# BMS_MAINBOARD.net
KiCad netlist of a schematic drawn in Altium Designer
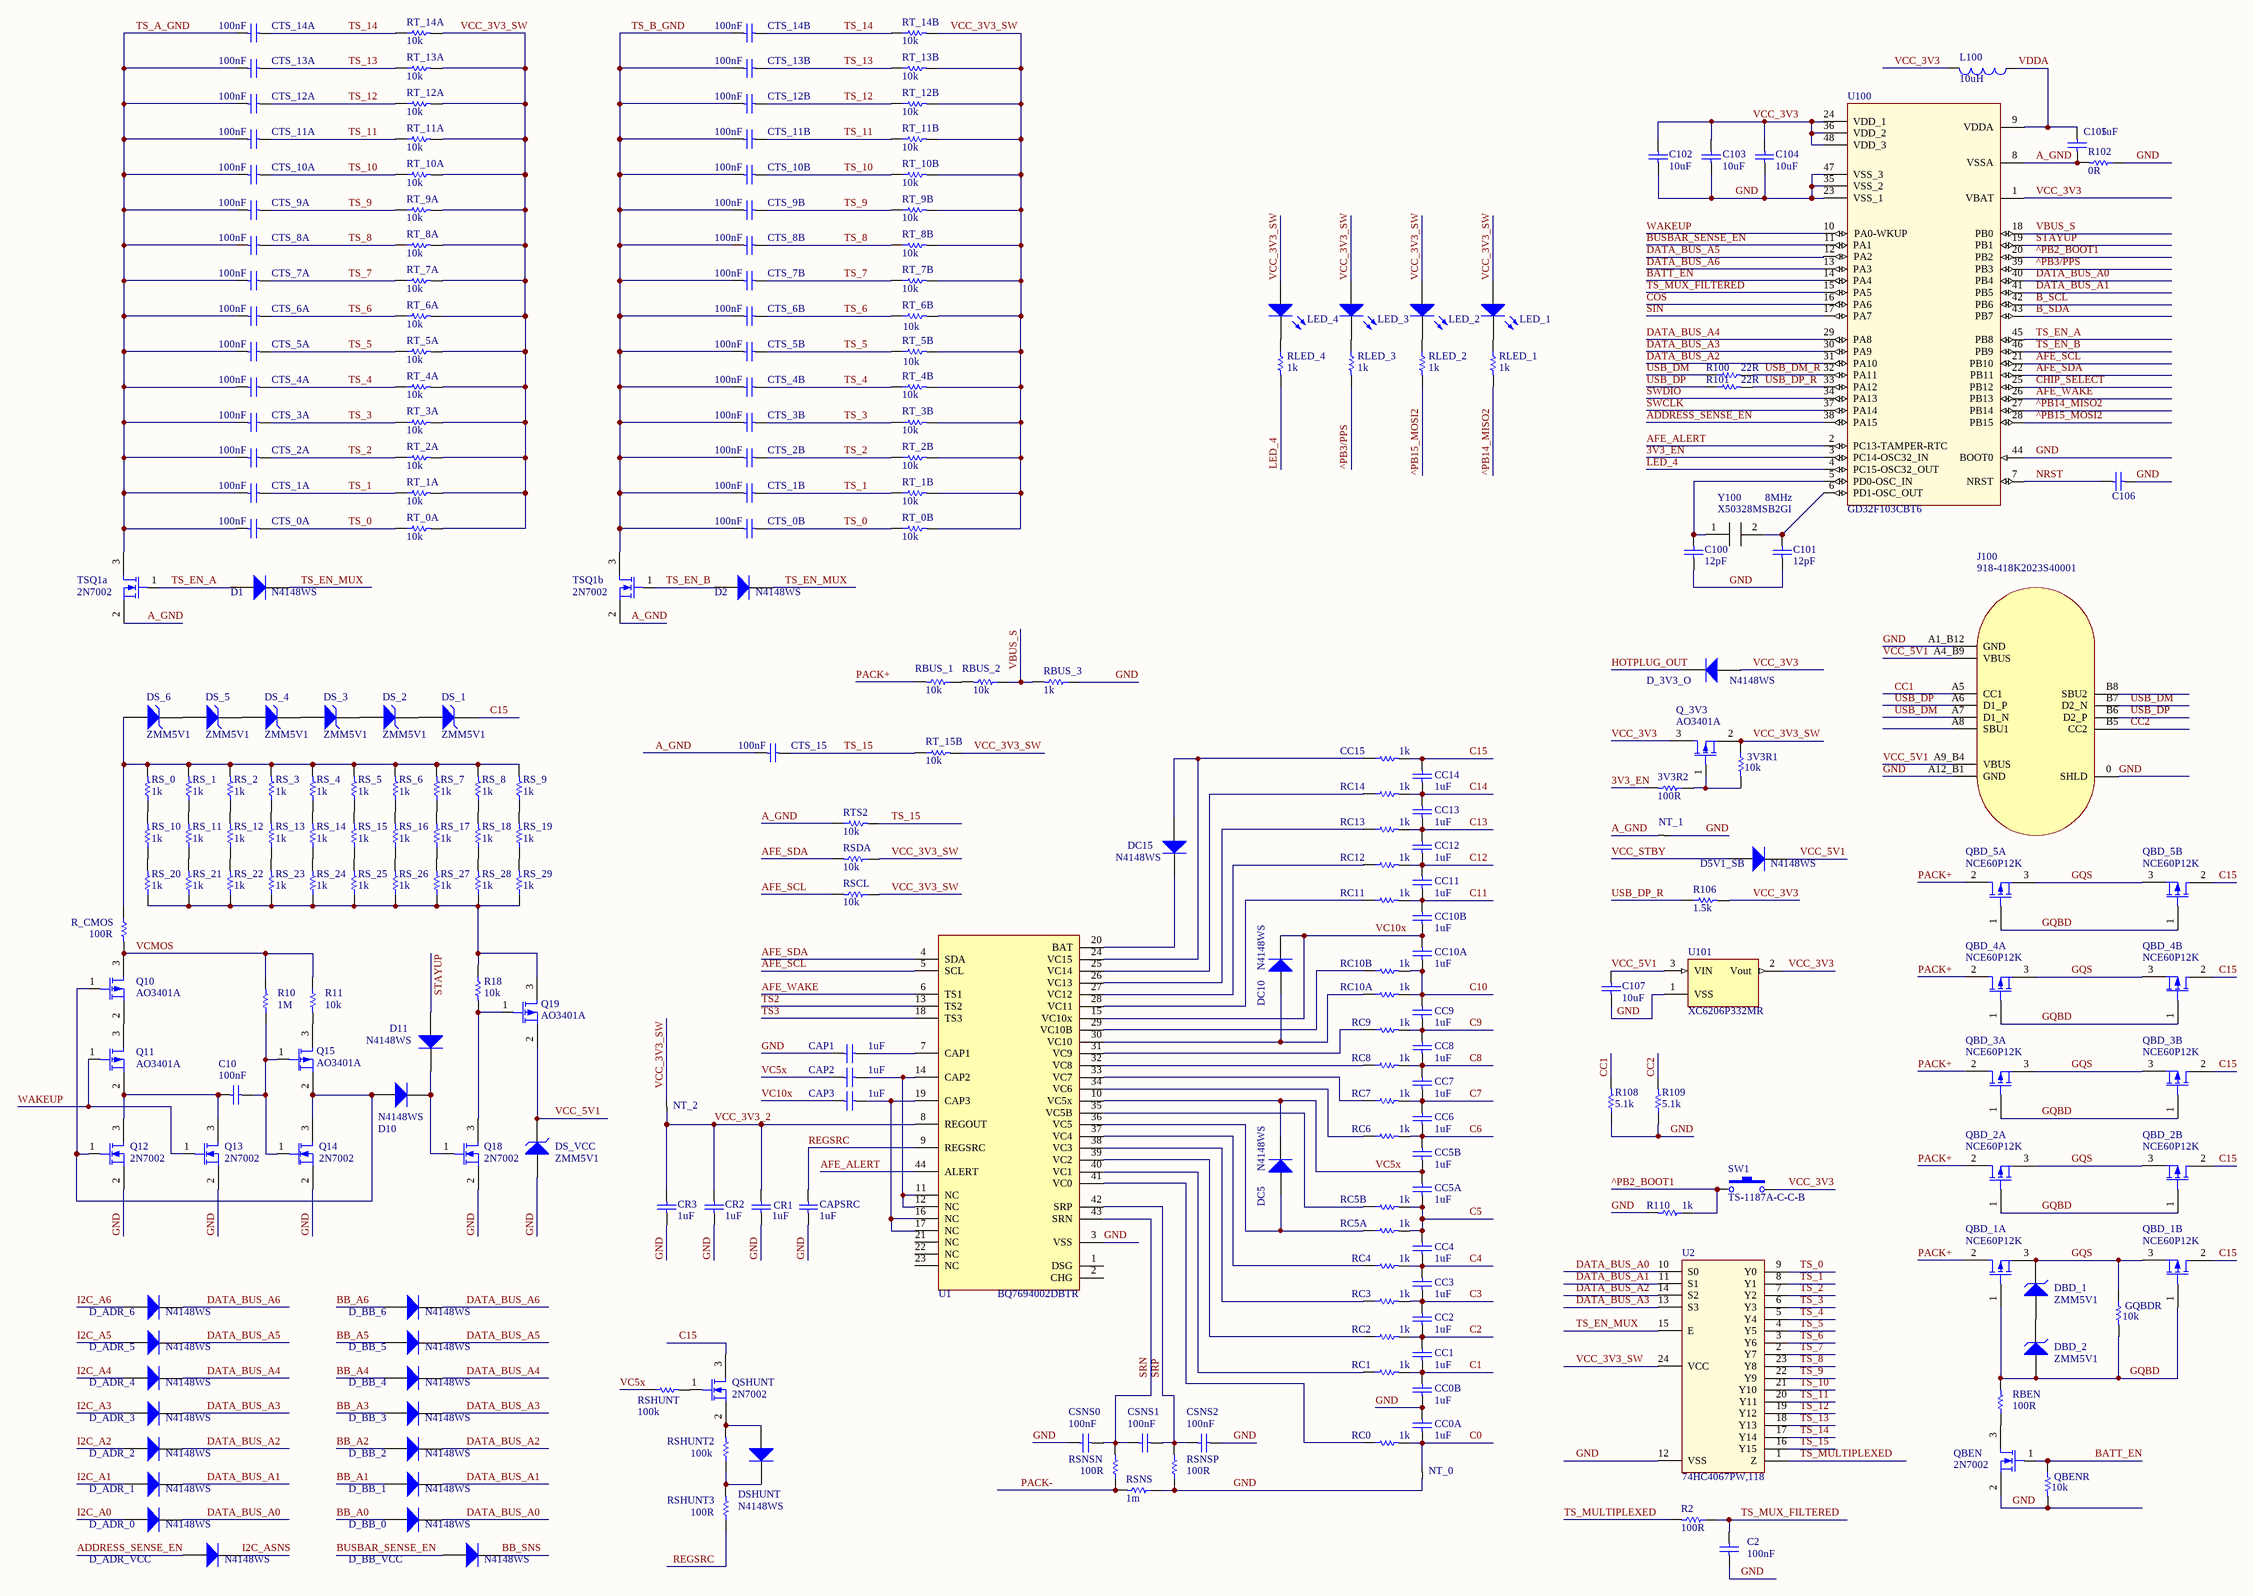
[diagram p0: BMS_MAINBOARD.SchDoc]

(export (version "E")
  (design (tool "Eeschema 10.0.6"))
  (components
    (comp (ref "3V3R1")
      (value "10k")
      (footprint "R_0402")
      (description "R - RESISTOR - SMD - 10k - 1% - 0402")
      (fields (field (name "LCSC PART #") "C25744") (field (name "Comment") "0402WGF1002TCE"))
      (libsource (lib "JLC_PCB") (part "0402WGF1002TCE"))
    )
    (comp (ref "3V3R2")
      (value "100R")
      (footprint "R_0402")
      (description "R - RESISTOR - SMD - 100R - 1% - 0402")
      (fields (field (name "LCSC PART #") "C25076") (field (name "Comment") "0402WGF1000TCE"))
      (libsource (lib "JLC_PCB") (part "0402WGF1000TCE"))
    )
    (comp (ref "C2")
      (value "100nF")
      (footprint "C_0402")
      (description "C - CAPACITOR - MLCC - 100nF - 16V - 0402")
      (fields (field (name "LCSC PART #") "C1525") (field (name "Comment") "CL05B104KO5NNNC"))
      (libsource (lib "JLC_PCB") (part "CL05B104KO5NNNC"))
    )
    (comp (ref "C10")
      (value "100nF")
      (footprint "C_0402")
      (description "C - CAPACITOR - MLCC - 100nF - 16V - 0402")
      (fields (field (name "LCSC PART #") "C1525") (field (name "Comment") "CL05B104KO5NNNC"))
      (libsource (lib "JLC_PCB") (part "CL05B104KO5NNNC"))
    )
    (comp (ref "C100")
      (value "12pF")
      (footprint "C_0402")
      (description "C - CAPACITOR - MLCC - 12pF - 50V - 0402")
      (fields (field (name "LCSC PART #") "C1547") (field (name "Comment") "0402CG120J500NT"))
      (libsource (lib "JLC_PCB") (part "0402CG120J500NT"))
    )
    (comp (ref "C101")
      (value "12pF")
      (footprint "C_0402")
      (description "C - CAPACITOR - MLCC - 12pF - 50V - 0402")
      (fields (field (name "LCSC PART #") "C1547") (field (name "Comment") "0402CG120J500NT"))
      (libsource (lib "JLC_PCB") (part "0402CG120J500NT"))
    )
    (comp (ref "C102")
      (value "10uF")
      (footprint "C_0402")
      (description "C - CAPACITOR - MLCC - 10uF - 6.3V - 0402")
      (fields (field (name "LCSC PART #") "C15525") (field (name "Comment") "CL05A106MQ5NUNC"))
      (libsource (lib "JLC_PCB") (part "CL05A106MQ5NUNC"))
    )
    (comp (ref "C103")
      (value "10uF")
      (footprint "C_0402")
      (description "C - CAPACITOR - MLCC - 10uF - 6.3V - 0402")
      (fields (field (name "LCSC PART #") "C15525") (field (name "Comment") "CL05A106MQ5NUNC"))
      (libsource (lib "JLC_PCB") (part "CL05A106MQ5NUNC"))
    )
    (comp (ref "C104")
      (value "10uF")
      (footprint "C_0402")
      (description "C - CAPACITOR - MLCC - 10uF - 6.3V - 0402")
      (fields (field (name "LCSC PART #") "C15525") (field (name "Comment") "CL05A106MQ5NUNC"))
      (libsource (lib "JLC_PCB") (part "CL05A106MQ5NUNC"))
    )
    (comp (ref "C105")
      (value "1uF")
      (footprint "C_0402")
      (description "C - CAPACITOR - MLCC - 1uF - 25V - 0402")
      (fields (field (name "LCSC PART #") "C52923") (field (name "Comment") "CL05A105KA5NQNC"))
      (libsource (lib "JLC_PCB") (part "CL05A105KA5NQNC"))
    )
    (comp (ref "C106")
      (value "0402CG101J500NT")
      (footprint "C_0402")
      (description "C - CAPACITOR - MLCC - 100pF - 50V - 0402")
      (fields (field (name "LCSC PART #") "C1546"))
      (libsource (lib "JLC_PCB") (part "0402CG101J500NT"))
    )
    (comp (ref "C107")
      (value "10uF")
      (footprint "C_0402")
      (description "C - CAPACITOR - MLCC - 10uF - 6.3V - 0402")
      (fields (field (name "LCSC PART #") "C15525") (field (name "Comment") "CL05A106MQ5NUNC"))
      (libsource (lib "JLC_PCB") (part "CL05A106MQ5NUNC"))
    )
    (comp (ref "CAP1")
      (value "1uF")
      (footprint "C_0402")
      (description "C - CAPACITOR - MLCC - 1uF - 25V - 0402")
      (fields (field (name "LCSC PART #") "C52923") (field (name "Comment") "CL05A105KA5NQNC"))
      (libsource (lib "JLC_PCB") (part "CL05A105KA5NQNC"))
    )
    (comp (ref "CAP2")
      (value "1uF")
      (footprint "C_0402")
      (description "C - CAPACITOR - MLCC - 1uF - 25V - 0402")
      (fields (field (name "LCSC PART #") "C52923") (field (name "Comment") "CL05A105KA5NQNC"))
      (libsource (lib "JLC_PCB") (part "CL05A105KA5NQNC"))
    )
    (comp (ref "CAP3")
      (value "1uF")
      (footprint "C_0402")
      (description "C - CAPACITOR - MLCC - 1uF - 25V - 0402")
      (fields (field (name "LCSC PART #") "C52923") (field (name "Comment") "CL05A105KA5NQNC"))
      (libsource (lib "JLC_PCB") (part "CL05A105KA5NQNC"))
    )
    (comp (ref "CAPSRC")
      (value "1uF")
      (footprint "C_0402")
      (description "C - CAPACITOR - MLCC - 1uF - 25V - 0402")
      (fields (field (name "LCSC PART #") "C52923") (field (name "Comment") "CL05A105KA5NQNC"))
      (libsource (lib "JLC_PCB") (part "CL05A105KA5NQNC"))
    )
    (comp (ref "CC0A")
      (value "1uF")
      (footprint "C_0402")
      (description "C - CAPACITOR - MLCC - 1uF - 25V - 0402")
      (fields (field (name "LCSC PART #") "C52923") (field (name "Comment") "CL05A105KA5NQNC"))
      (libsource (lib "JLC_PCB") (part "CL05A105KA5NQNC"))
    )
    (comp (ref "CC0B")
      (value "1uF")
      (footprint "C_0402")
      (description "C - CAPACITOR - MLCC - 1uF - 25V - 0402")
      (fields (field (name "LCSC PART #") "C52923") (field (name "Comment") "CL05A105KA5NQNC"))
      (libsource (lib "JLC_PCB") (part "CL05A105KA5NQNC"))
    )
    (comp (ref "CC1")
      (value "1uF")
      (footprint "C_0402")
      (description "C - CAPACITOR - MLCC - 1uF - 25V - 0402")
      (fields (field (name "LCSC PART #") "C52923") (field (name "Comment") "CL05A105KA5NQNC"))
      (libsource (lib "JLC_PCB") (part "CL05A105KA5NQNC"))
    )
    (comp (ref "CC2")
      (value "1uF")
      (footprint "C_0402")
      (description "C - CAPACITOR - MLCC - 1uF - 25V - 0402")
      (fields (field (name "LCSC PART #") "C52923") (field (name "Comment") "CL05A105KA5NQNC"))
      (libsource (lib "JLC_PCB") (part "CL05A105KA5NQNC"))
    )
    (comp (ref "CC3")
      (value "1uF")
      (footprint "C_0402")
      (description "C - CAPACITOR - MLCC - 1uF - 25V - 0402")
      (fields (field (name "LCSC PART #") "C52923") (field (name "Comment") "CL05A105KA5NQNC"))
      (libsource (lib "JLC_PCB") (part "CL05A105KA5NQNC"))
    )
    (comp (ref "CC4")
      (value "1uF")
      (footprint "C_0402")
      (description "C - CAPACITOR - MLCC - 1uF - 25V - 0402")
      (fields (field (name "LCSC PART #") "C52923") (field (name "Comment") "CL05A105KA5NQNC"))
      (libsource (lib "JLC_PCB") (part "CL05A105KA5NQNC"))
    )
    (comp (ref "CC5A")
      (value "1uF")
      (footprint "C_0402")
      (description "C - CAPACITOR - MLCC - 1uF - 25V - 0402")
      (fields (field (name "LCSC PART #") "C52923") (field (name "Comment") "CL05A105KA5NQNC"))
      (libsource (lib "JLC_PCB") (part "CL05A105KA5NQNC"))
    )
    (comp (ref "CC5B")
      (value "1uF")
      (footprint "C_0402")
      (description "C - CAPACITOR - MLCC - 1uF - 25V - 0402")
      (fields (field (name "LCSC PART #") "C52923") (field (name "Comment") "CL05A105KA5NQNC"))
      (libsource (lib "JLC_PCB") (part "CL05A105KA5NQNC"))
    )
    (comp (ref "CC6")
      (value "1uF")
      (footprint "C_0402")
      (description "C - CAPACITOR - MLCC - 1uF - 25V - 0402")
      (fields (field (name "LCSC PART #") "C52923") (field (name "Comment") "CL05A105KA5NQNC"))
      (libsource (lib "JLC_PCB") (part "CL05A105KA5NQNC"))
    )
    (comp (ref "CC7")
      (value "1uF")
      (footprint "C_0402")
      (description "C - CAPACITOR - MLCC - 1uF - 25V - 0402")
      (fields (field (name "LCSC PART #") "C52923") (field (name "Comment") "CL05A105KA5NQNC"))
      (libsource (lib "JLC_PCB") (part "CL05A105KA5NQNC"))
    )
    (comp (ref "CC8")
      (value "1uF")
      (footprint "C_0402")
      (description "C - CAPACITOR - MLCC - 1uF - 25V - 0402")
      (fields (field (name "LCSC PART #") "C52923") (field (name "Comment") "CL05A105KA5NQNC"))
      (libsource (lib "JLC_PCB") (part "CL05A105KA5NQNC"))
    )
    (comp (ref "CC9")
      (value "1uF")
      (footprint "C_0402")
      (description "C - CAPACITOR - MLCC - 1uF - 25V - 0402")
      (fields (field (name "LCSC PART #") "C52923") (field (name "Comment") "CL05A105KA5NQNC"))
      (libsource (lib "JLC_PCB") (part "CL05A105KA5NQNC"))
    )
    (comp (ref "CC10A")
      (value "1uF")
      (footprint "C_0402")
      (description "C - CAPACITOR - MLCC - 1uF - 25V - 0402")
      (fields (field (name "LCSC PART #") "C52923") (field (name "Comment") "CL05A105KA5NQNC"))
      (libsource (lib "JLC_PCB") (part "CL05A105KA5NQNC"))
    )
    (comp (ref "CC10B")
      (value "1uF")
      (footprint "C_0402")
      (description "C - CAPACITOR - MLCC - 1uF - 25V - 0402")
      (fields (field (name "LCSC PART #") "C52923") (field (name "Comment") "CL05A105KA5NQNC"))
      (libsource (lib "JLC_PCB") (part "CL05A105KA5NQNC"))
    )
    (comp (ref "CC11")
      (value "1uF")
      (footprint "C_0402")
      (description "C - CAPACITOR - MLCC - 1uF - 25V - 0402")
      (fields (field (name "LCSC PART #") "C52923") (field (name "Comment") "CL05A105KA5NQNC"))
      (libsource (lib "JLC_PCB") (part "CL05A105KA5NQNC"))
    )
    (comp (ref "CC12")
      (value "1uF")
      (footprint "C_0402")
      (description "C - CAPACITOR - MLCC - 1uF - 25V - 0402")
      (fields (field (name "LCSC PART #") "C52923") (field (name "Comment") "CL05A105KA5NQNC"))
      (libsource (lib "JLC_PCB") (part "CL05A105KA5NQNC"))
    )
    (comp (ref "CC13")
      (value "1uF")
      (footprint "C_0402")
      (description "C - CAPACITOR - MLCC - 1uF - 25V - 0402")
      (fields (field (name "LCSC PART #") "C52923") (field (name "Comment") "CL05A105KA5NQNC"))
      (libsource (lib "JLC_PCB") (part "CL05A105KA5NQNC"))
    )
    (comp (ref "CC14")
      (value "1uF")
      (footprint "C_0402")
      (description "C - CAPACITOR - MLCC - 1uF - 25V - 0402")
      (fields (field (name "LCSC PART #") "C52923") (field (name "Comment") "CL05A105KA5NQNC"))
      (libsource (lib "JLC_PCB") (part "CL05A105KA5NQNC"))
    )
    (comp (ref "CC15")
      (value "1k")
      (footprint "R_0402")
      (description "R - RESISTOR - SMD - 1k - 1% - 0402")
      (fields (field (name "LCSC PART #") "C11702") (field (name "Comment") "0402WGF1001TCE"))
      (libsource (lib "JLC_PCB") (part "0402WGF1001TCE"))
    )
    (comp (ref "CR1")
      (value "1uF")
      (footprint "C_0402")
      (description "C - CAPACITOR - MLCC - 1uF - 25V - 0402")
      (fields (field (name "LCSC PART #") "C52923") (field (name "Comment") "CL05A105KA5NQNC"))
      (libsource (lib "JLC_PCB") (part "CL05A105KA5NQNC"))
    )
    (comp (ref "CR2")
      (value "1uF")
      (footprint "C_0402")
      (description "C - CAPACITOR - MLCC - 1uF - 25V - 0402")
      (fields (field (name "LCSC PART #") "C52923") (field (name "Comment") "CL05A105KA5NQNC"))
      (libsource (lib "JLC_PCB") (part "CL05A105KA5NQNC"))
    )
    (comp (ref "CR3")
      (value "1uF")
      (footprint "C_0402")
      (description "C - CAPACITOR - MLCC - 1uF - 25V - 0402")
      (fields (field (name "LCSC PART #") "C52923") (field (name "Comment") "CL05A105KA5NQNC"))
      (libsource (lib "JLC_PCB") (part "CL05A105KA5NQNC"))
    )
    (comp (ref "CSNS0")
      (value "100nF")
      (footprint "C_0402")
      (description "C - CAPACITOR - MLCC - 100nF - 16V - 0402")
      (fields (field (name "LCSC PART #") "C1525") (field (name "Comment") "CL05B104KO5NNNC"))
      (libsource (lib "JLC_PCB") (part "CL05B104KO5NNNC"))
    )
    (comp (ref "CSNS1")
      (value "100nF")
      (footprint "C_0402")
      (description "C - CAPACITOR - MLCC - 100nF - 16V - 0402")
      (fields (field (name "LCSC PART #") "C1525") (field (name "Comment") "CL05B104KO5NNNC"))
      (libsource (lib "JLC_PCB") (part "CL05B104KO5NNNC"))
    )
    (comp (ref "CSNS2")
      (value "100nF")
      (footprint "C_0402")
      (description "C - CAPACITOR - MLCC - 100nF - 16V - 0402")
      (fields (field (name "LCSC PART #") "C1525") (field (name "Comment") "CL05B104KO5NNNC"))
      (libsource (lib "JLC_PCB") (part "CL05B104KO5NNNC"))
    )
    (comp (ref "CTS_0A")
      (value "100nF")
      (footprint "C_0402")
      (description "C - CAPACITOR - MLCC - 100nF - 16V - 0402")
      (fields (field (name "LCSC PART #") "C1525") (field (name "Comment") "CL05B104KO5NNNC"))
      (libsource (lib "JLC_PCB") (part "CL05B104KO5NNNC"))
    )
    (comp (ref "CTS_0B")
      (value "100nF")
      (footprint "C_0402")
      (description "C - CAPACITOR - MLCC - 100nF - 16V - 0402")
      (fields (field (name "LCSC PART #") "C1525") (field (name "Comment") "CL05B104KO5NNNC"))
      (libsource (lib "JLC_PCB") (part "CL05B104KO5NNNC"))
    )
    (comp (ref "CTS_1A")
      (value "100nF")
      (footprint "C_0402")
      (description "C - CAPACITOR - MLCC - 100nF - 16V - 0402")
      (fields (field (name "LCSC PART #") "C1525") (field (name "Comment") "CL05B104KO5NNNC"))
      (libsource (lib "JLC_PCB") (part "CL05B104KO5NNNC"))
    )
    (comp (ref "CTS_1B")
      (value "100nF")
      (footprint "C_0402")
      (description "C - CAPACITOR - MLCC - 100nF - 16V - 0402")
      (fields (field (name "LCSC PART #") "C1525") (field (name "Comment") "CL05B104KO5NNNC"))
      (libsource (lib "JLC_PCB") (part "CL05B104KO5NNNC"))
    )
    (comp (ref "CTS_2A")
      (value "100nF")
      (footprint "C_0402")
      (description "C - CAPACITOR - MLCC - 100nF - 16V - 0402")
      (fields (field (name "LCSC PART #") "C1525") (field (name "Comment") "CL05B104KO5NNNC"))
      (libsource (lib "JLC_PCB") (part "CL05B104KO5NNNC"))
    )
    (comp (ref "CTS_2B")
      (value "100nF")
      (footprint "C_0402")
      (description "C - CAPACITOR - MLCC - 100nF - 16V - 0402")
      (fields (field (name "LCSC PART #") "C1525") (field (name "Comment") "CL05B104KO5NNNC"))
      (libsource (lib "JLC_PCB") (part "CL05B104KO5NNNC"))
    )
    (comp (ref "CTS_3A")
      (value "100nF")
      (footprint "C_0402")
      (description "C - CAPACITOR - MLCC - 100nF - 16V - 0402")
      (fields (field (name "LCSC PART #") "C1525") (field (name "Comment") "CL05B104KO5NNNC"))
      (libsource (lib "JLC_PCB") (part "CL05B104KO5NNNC"))
    )
    (comp (ref "CTS_3B")
      (value "100nF")
      (footprint "C_0402")
      (description "C - CAPACITOR - MLCC - 100nF - 16V - 0402")
      (fields (field (name "LCSC PART #") "C1525") (field (name "Comment") "CL05B104KO5NNNC"))
      (libsource (lib "JLC_PCB") (part "CL05B104KO5NNNC"))
    )
    (comp (ref "CTS_4A")
      (value "100nF")
      (footprint "C_0402")
      (description "C - CAPACITOR - MLCC - 100nF - 16V - 0402")
      (fields (field (name "LCSC PART #") "C1525") (field (name "Comment") "CL05B104KO5NNNC"))
      (libsource (lib "JLC_PCB") (part "CL05B104KO5NNNC"))
    )
    (comp (ref "CTS_4B")
      (value "100nF")
      (footprint "C_0402")
      (description "C - CAPACITOR - MLCC - 100nF - 16V - 0402")
      (fields (field (name "LCSC PART #") "C1525") (field (name "Comment") "CL05B104KO5NNNC"))
      (libsource (lib "JLC_PCB") (part "CL05B104KO5NNNC"))
    )
    (comp (ref "CTS_5A")
      (value "100nF")
      (footprint "C_0402")
      (description "C - CAPACITOR - MLCC - 100nF - 16V - 0402")
      (fields (field (name "LCSC PART #") "C1525") (field (name "Comment") "CL05B104KO5NNNC"))
      (libsource (lib "JLC_PCB") (part "CL05B104KO5NNNC"))
    )
    (comp (ref "CTS_5B")
      (value "100nF")
      (footprint "C_0402")
      (description "C - CAPACITOR - MLCC - 100nF - 16V - 0402")
      (fields (field (name "LCSC PART #") "C1525") (field (name "Comment") "CL05B104KO5NNNC"))
      (libsource (lib "JLC_PCB") (part "CL05B104KO5NNNC"))
    )
    (comp (ref "CTS_6A")
      (value "100nF")
      (footprint "C_0402")
      (description "C - CAPACITOR - MLCC - 100nF - 16V - 0402")
      (fields (field (name "LCSC PART #") "C1525") (field (name "Comment") "CL05B104KO5NNNC"))
      (libsource (lib "JLC_PCB") (part "CL05B104KO5NNNC"))
    )
    (comp (ref "CTS_6B")
      (value "100nF")
      (footprint "C_0402")
      (description "C - CAPACITOR - MLCC - 100nF - 16V - 0402")
      (fields (field (name "LCSC PART #") "C1525") (field (name "Comment") "CL05B104KO5NNNC"))
      (libsource (lib "JLC_PCB") (part "CL05B104KO5NNNC"))
    )
    (comp (ref "CTS_7A")
      (value "100nF")
      (footprint "C_0402")
      (description "C - CAPACITOR - MLCC - 100nF - 16V - 0402")
      (fields (field (name "LCSC PART #") "C1525") (field (name "Comment") "CL05B104KO5NNNC"))
      (libsource (lib "JLC_PCB") (part "CL05B104KO5NNNC"))
    )
    (comp (ref "CTS_7B")
      (value "100nF")
      (footprint "C_0402")
      (description "C - CAPACITOR - MLCC - 100nF - 16V - 0402")
      (fields (field (name "LCSC PART #") "C1525") (field (name "Comment") "CL05B104KO5NNNC"))
      (libsource (lib "JLC_PCB") (part "CL05B104KO5NNNC"))
    )
    (comp (ref "CTS_8A")
      (value "100nF")
      (footprint "C_0402")
      (description "C - CAPACITOR - MLCC - 100nF - 16V - 0402")
      (fields (field (name "LCSC PART #") "C1525") (field (name "Comment") "CL05B104KO5NNNC"))
      (libsource (lib "JLC_PCB") (part "CL05B104KO5NNNC"))
    )
    (comp (ref "CTS_8B")
      (value "100nF")
      (footprint "C_0402")
      (description "C - CAPACITOR - MLCC - 100nF - 16V - 0402")
      (fields (field (name "LCSC PART #") "C1525") (field (name "Comment") "CL05B104KO5NNNC"))
      (libsource (lib "JLC_PCB") (part "CL05B104KO5NNNC"))
    )
    (comp (ref "CTS_9A")
      (value "100nF")
      (footprint "C_0402")
      (description "C - CAPACITOR - MLCC - 100nF - 16V - 0402")
      (fields (field (name "LCSC PART #") "C1525") (field (name "Comment") "CL05B104KO5NNNC"))
      (libsource (lib "JLC_PCB") (part "CL05B104KO5NNNC"))
    )
    (comp (ref "CTS_9B")
      (value "100nF")
      (footprint "C_0402")
      (description "C - CAPACITOR - MLCC - 100nF - 16V - 0402")
      (fields (field (name "LCSC PART #") "C1525") (field (name "Comment") "CL05B104KO5NNNC"))
      (libsource (lib "JLC_PCB") (part "CL05B104KO5NNNC"))
    )
    (comp (ref "CTS_10A")
      (value "100nF")
      (footprint "C_0402")
      (description "C - CAPACITOR - MLCC - 100nF - 16V - 0402")
      (fields (field (name "LCSC PART #") "C1525") (field (name "Comment") "CL05B104KO5NNNC"))
      (libsource (lib "JLC_PCB") (part "CL05B104KO5NNNC"))
    )
    (comp (ref "CTS_10B")
      (value "100nF")
      (footprint "C_0402")
      (description "C - CAPACITOR - MLCC - 100nF - 16V - 0402")
      (fields (field (name "LCSC PART #") "C1525") (field (name "Comment") "CL05B104KO5NNNC"))
      (libsource (lib "JLC_PCB") (part "CL05B104KO5NNNC"))
    )
    (comp (ref "CTS_11A")
      (value "100nF")
      (footprint "C_0402")
      (description "C - CAPACITOR - MLCC - 100nF - 16V - 0402")
      (fields (field (name "LCSC PART #") "C1525") (field (name "Comment") "CL05B104KO5NNNC"))
      (libsource (lib "JLC_PCB") (part "CL05B104KO5NNNC"))
    )
    (comp (ref "CTS_11B")
      (value "100nF")
      (footprint "C_0402")
      (description "C - CAPACITOR - MLCC - 100nF - 16V - 0402")
      (fields (field (name "LCSC PART #") "C1525") (field (name "Comment") "CL05B104KO5NNNC"))
      (libsource (lib "JLC_PCB") (part "CL05B104KO5NNNC"))
    )
    (comp (ref "CTS_12A")
      (value "100nF")
      (footprint "C_0402")
      (description "C - CAPACITOR - MLCC - 100nF - 16V - 0402")
      (fields (field (name "LCSC PART #") "C1525") (field (name "Comment") "CL05B104KO5NNNC"))
      (libsource (lib "JLC_PCB") (part "CL05B104KO5NNNC"))
    )
    (comp (ref "CTS_12B")
      (value "100nF")
      (footprint "C_0402")
      (description "C - CAPACITOR - MLCC - 100nF - 16V - 0402")
      (fields (field (name "LCSC PART #") "C1525") (field (name "Comment") "CL05B104KO5NNNC"))
      (libsource (lib "JLC_PCB") (part "CL05B104KO5NNNC"))
    )
    (comp (ref "CTS_13A")
      (value "100nF")
      (footprint "C_0402")
      (description "C - CAPACITOR - MLCC - 100nF - 16V - 0402")
      (fields (field (name "LCSC PART #") "C1525") (field (name "Comment") "CL05B104KO5NNNC"))
      (libsource (lib "JLC_PCB") (part "CL05B104KO5NNNC"))
    )
    (comp (ref "CTS_13B")
      (value "100nF")
      (footprint "C_0402")
      (description "C - CAPACITOR - MLCC - 100nF - 16V - 0402")
      (fields (field (name "LCSC PART #") "C1525") (field (name "Comment") "CL05B104KO5NNNC"))
      (libsource (lib "JLC_PCB") (part "CL05B104KO5NNNC"))
    )
    (comp (ref "CTS_14A")
      (value "100nF")
      (footprint "C_0402")
      (description "C - CAPACITOR - MLCC - 100nF - 16V - 0402")
      (fields (field (name "LCSC PART #") "C1525") (field (name "Comment") "CL05B104KO5NNNC"))
      (libsource (lib "JLC_PCB") (part "CL05B104KO5NNNC"))
    )
    (comp (ref "CTS_14B")
      (value "100nF")
      (footprint "C_0402")
      (description "C - CAPACITOR - MLCC - 100nF - 16V - 0402")
      (fields (field (name "LCSC PART #") "C1525") (field (name "Comment") "CL05B104KO5NNNC"))
      (libsource (lib "JLC_PCB") (part "CL05B104KO5NNNC"))
    )
    (comp (ref "CTS_15")
      (value "100nF")
      (footprint "C_0402")
      (description "C - CAPACITOR - MLCC - 100nF - 16V - 0402")
      (fields (field (name "LCSC PART #") "C1525") (field (name "Comment") "CL05B104KO5NNNC"))
      (libsource (lib "JLC_PCB") (part "CL05B104KO5NNNC"))
    )
    (comp (ref "D1")
      (value "N4148WS")
      (footprint "SOD-323")
      (description "D - DIODE - FAST TRR - 100V - 150mA - 4ns")
      (fields (field (name "LCSC PART #") "C2128"))
      (libsource (lib "JLC_PCB") (part "N4148WS"))
    )
    (comp (ref "D2")
      (value "N4148WS")
      (footprint "SOD-323")
      (description "D - DIODE - FAST TRR - 100V - 150mA - 4ns")
      (fields (field (name "LCSC PART #") "C2128"))
      (libsource (lib "JLC_PCB") (part "N4148WS"))
    )
    (comp (ref "D5V1_SB")
      (value "N4148WS")
      (footprint "SOD-323")
      (description "D - DIODE - FAST TRR - 100V - 150mA - 4ns")
      (fields (field (name "LCSC PART #") "C2128"))
      (libsource (lib "JLC_PCB") (part "N4148WS"))
    )
    (comp (ref "D10")
      (value "N4148WS")
      (footprint "SOD-323")
      (description "D - DIODE - FAST TRR - 100V - 150mA - 4ns")
      (fields (field (name "LCSC PART #") "C2128"))
      (libsource (lib "JLC_PCB") (part "N4148WS"))
    )
    (comp (ref "D11")
      (value "N4148WS")
      (footprint "SOD-323")
      (description "D - DIODE - FAST TRR - 100V - 150mA - 4ns")
      (fields (field (name "LCSC PART #") "C2128"))
      (libsource (lib "JLC_PCB") (part "N4148WS"))
    )
    (comp (ref "DBD_1")
      (value "ZMM5V1")
      (footprint "DO-213AA")
      (description "D - DIODE - ZENER - 5.1V - 500mW")
      (fields (field (name "LCSC PART #") "C8061"))
      (libsource (lib "JLC_PCB") (part "ZMM5V1"))
    )
    (comp (ref "DBD_2")
      (value "ZMM5V1")
      (footprint "DO-213AA")
      (description "D - DIODE - ZENER - 5.1V - 500mW")
      (fields (field (name "LCSC PART #") "C8061"))
      (libsource (lib "JLC_PCB") (part "ZMM5V1"))
    )
    (comp (ref "DC5")
      (value "N4148WS")
      (footprint "SOD-323")
      (description "D - DIODE - FAST TRR - 100V - 150mA - 4ns")
      (fields (field (name "LCSC PART #") "C2128"))
      (libsource (lib "JLC_PCB") (part "N4148WS"))
    )
    (comp (ref "DC10")
      (value "N4148WS")
      (footprint "SOD-323")
      (description "D - DIODE - FAST TRR - 100V - 150mA - 4ns")
      (fields (field (name "LCSC PART #") "C2128"))
      (libsource (lib "JLC_PCB") (part "N4148WS"))
    )
    (comp (ref "DC15")
      (value "N4148WS")
      (footprint "SOD-323")
      (description "D - DIODE - FAST TRR - 100V - 150mA - 4ns")
      (fields (field (name "LCSC PART #") "C2128"))
      (libsource (lib "JLC_PCB") (part "N4148WS"))
    )
    (comp (ref "DSHUNT")
      (value "N4148WS")
      (footprint "SOD-323")
      (description "D - DIODE - FAST TRR - 100V - 150mA - 4ns")
      (fields (field (name "LCSC PART #") "C2128"))
      (libsource (lib "JLC_PCB") (part "N4148WS"))
    )
    (comp (ref "DS_1")
      (value "ZMM5V1")
      (footprint "DO-213AA")
      (description "D - DIODE - ZENER - 5.1V - 500mW")
      (fields (field (name "LCSC PART #") "C8061"))
      (libsource (lib "JLC_PCB") (part "ZMM5V1"))
    )
    (comp (ref "DS_2")
      (value "ZMM5V1")
      (footprint "DO-213AA")
      (description "D - DIODE - ZENER - 5.1V - 500mW")
      (fields (field (name "LCSC PART #") "C8061"))
      (libsource (lib "JLC_PCB") (part "ZMM5V1"))
    )
    (comp (ref "DS_3")
      (value "ZMM5V1")
      (footprint "DO-213AA")
      (description "D - DIODE - ZENER - 5.1V - 500mW")
      (fields (field (name "LCSC PART #") "C8061"))
      (libsource (lib "JLC_PCB") (part "ZMM5V1"))
    )
    (comp (ref "DS_4")
      (value "ZMM5V1")
      (footprint "DO-213AA")
      (description "D - DIODE - ZENER - 5.1V - 500mW")
      (fields (field (name "LCSC PART #") "C8061"))
      (libsource (lib "JLC_PCB") (part "ZMM5V1"))
    )
    (comp (ref "DS_5")
      (value "ZMM5V1")
      (footprint "DO-213AA")
      (description "D - DIODE - ZENER - 5.1V - 500mW")
      (fields (field (name "LCSC PART #") "C8061"))
      (libsource (lib "JLC_PCB") (part "ZMM5V1"))
    )
    (comp (ref "DS_6")
      (value "ZMM5V1")
      (footprint "DO-213AA")
      (description "D - DIODE - ZENER - 5.1V - 500mW")
      (fields (field (name "LCSC PART #") "C8061"))
      (libsource (lib "JLC_PCB") (part "ZMM5V1"))
    )
    (comp (ref "DS_VCC")
      (value "ZMM5V1")
      (footprint "DO-213AA")
      (description "D - DIODE - ZENER - 5.1V - 500mW")
      (fields (field (name "LCSC PART #") "C8061"))
      (libsource (lib "JLC_PCB") (part "ZMM5V1"))
    )
    (comp (ref "D_3V3_O")
      (value "N4148WS")
      (footprint "SOD-323")
      (description "D - DIODE - FAST TRR - 100V - 150mA - 4ns")
      (fields (field (name "LCSC PART #") "C2128"))
      (libsource (lib "JLC_PCB") (part "N4148WS"))
    )
    (comp (ref "D_ADR_0")
      (value "N4148WS")
      (footprint "SOD-323")
      (description "D - DIODE - FAST TRR - 100V - 150mA - 4ns")
      (fields (field (name "LCSC PART #") "C2128"))
      (libsource (lib "JLC_PCB") (part "N4148WS"))
    )
    (comp (ref "D_ADR_1")
      (value "N4148WS")
      (footprint "SOD-323")
      (description "D - DIODE - FAST TRR - 100V - 150mA - 4ns")
      (fields (field (name "LCSC PART #") "C2128"))
      (libsource (lib "JLC_PCB") (part "N4148WS"))
    )
    (comp (ref "D_ADR_2")
      (value "N4148WS")
      (footprint "SOD-323")
      (description "D - DIODE - FAST TRR - 100V - 150mA - 4ns")
      (fields (field (name "LCSC PART #") "C2128"))
      (libsource (lib "JLC_PCB") (part "N4148WS"))
    )
    (comp (ref "D_ADR_3")
      (value "N4148WS")
      (footprint "SOD-323")
      (description "D - DIODE - FAST TRR - 100V - 150mA - 4ns")
      (fields (field (name "LCSC PART #") "C2128"))
      (libsource (lib "JLC_PCB") (part "N4148WS"))
    )
    (comp (ref "D_ADR_4")
      (value "N4148WS")
      (footprint "SOD-323")
      (description "D - DIODE - FAST TRR - 100V - 150mA - 4ns")
      (fields (field (name "LCSC PART #") "C2128"))
      (libsource (lib "JLC_PCB") (part "N4148WS"))
    )
    (comp (ref "D_ADR_5")
      (value "N4148WS")
      (footprint "SOD-323")
      (description "D - DIODE - FAST TRR - 100V - 150mA - 4ns")
      (fields (field (name "LCSC PART #") "C2128"))
      (libsource (lib "JLC_PCB") (part "N4148WS"))
    )
    (comp (ref "D_ADR_6")
      (value "N4148WS")
      (footprint "SOD-323")
      (description "D - DIODE - FAST TRR - 100V - 150mA - 4ns")
      (fields (field (name "LCSC PART #") "C2128"))
      (libsource (lib "JLC_PCB") (part "N4148WS"))
    )
    (comp (ref "D_ADR_VCC")
      (value "N4148WS")
      (footprint "SOD-323")
      (description "D - DIODE - FAST TRR - 100V - 150mA - 4ns")
      (fields (field (name "LCSC PART #") "C2128"))
      (libsource (lib "JLC_PCB") (part "N4148WS"))
    )
    (comp (ref "D_BB_0")
      (value "N4148WS")
      (footprint "SOD-323")
      (description "D - DIODE - FAST TRR - 100V - 150mA - 4ns")
      (fields (field (name "LCSC PART #") "C2128"))
      (libsource (lib "JLC_PCB") (part "N4148WS"))
    )
    (comp (ref "D_BB_1")
      (value "N4148WS")
      (footprint "SOD-323")
      (description "D - DIODE - FAST TRR - 100V - 150mA - 4ns")
      (fields (field (name "LCSC PART #") "C2128"))
      (libsource (lib "JLC_PCB") (part "N4148WS"))
    )
    (comp (ref "D_BB_2")
      (value "N4148WS")
      (footprint "SOD-323")
      (description "D - DIODE - FAST TRR - 100V - 150mA - 4ns")
      (fields (field (name "LCSC PART #") "C2128"))
      (libsource (lib "JLC_PCB") (part "N4148WS"))
    )
    (comp (ref "D_BB_3")
      (value "N4148WS")
      (footprint "SOD-323")
      (description "D - DIODE - FAST TRR - 100V - 150mA - 4ns")
      (fields (field (name "LCSC PART #") "C2128"))
      (libsource (lib "JLC_PCB") (part "N4148WS"))
    )
    (comp (ref "D_BB_4")
      (value "N4148WS")
      (footprint "SOD-323")
      (description "D - DIODE - FAST TRR - 100V - 150mA - 4ns")
      (fields (field (name "LCSC PART #") "C2128"))
      (libsource (lib "JLC_PCB") (part "N4148WS"))
    )
    (comp (ref "D_BB_5")
      (value "N4148WS")
      (footprint "SOD-323")
      (description "D - DIODE - FAST TRR - 100V - 150mA - 4ns")
      (fields (field (name "LCSC PART #") "C2128"))
      (libsource (lib "JLC_PCB") (part "N4148WS"))
    )
    (comp (ref "D_BB_6")
      (value "N4148WS")
      (footprint "SOD-323")
      (description "D - DIODE - FAST TRR - 100V - 150mA - 4ns")
      (fields (field (name "LCSC PART #") "C2128"))
      (libsource (lib "JLC_PCB") (part "N4148WS"))
    )
    (comp (ref "D_BB_VCC")
      (value "N4148WS")
      (footprint "SOD-323")
      (description "D - DIODE - FAST TRR - 100V - 150mA - 4ns")
      (fields (field (name "LCSC PART #") "C2128"))
      (libsource (lib "JLC_PCB") (part "N4148WS"))
    )
    (comp (ref "GQBDR")
      (value "10k")
      (footprint "R_0402")
      (description "R - RESISTOR - SMD - 10k - 1% - 0402")
      (fields (field (name "LCSC PART #") "C25744") (field (name "Comment") "0402WGF1002TCE"))
      (libsource (lib "JLC_PCB") (part "0402WGF1002TCE"))
    )
    (comp (ref "J100")
      (value "918-418K2023S40001")
      (footprint "DX07S016JA1R1500")
      (description "J - JACK - USB - Type C - Recepticle - SMT - 90°")
      (fields (field (name "LCSC PART #") "C167321"))
      (libsource (lib "JLC_PCB") (part "918-418K2023S40001"))
    )
    (comp (ref "L100")
      (value "10uH")
      (footprint "L_0603")
      (description "L - INDUCTOR - 10uH - 0603")
      (fields (field (name "LCSC PART #") "C1035") (field (name "Comment") "SDFL1608S100KTF"))
      (libsource (lib "JLC_PCB") (part "SDFL1608S100KTF"))
    )
    (comp (ref "LED_1")
      (value "19-21UYC/S530-A4/TR8")
      (footprint "D_0603")
      (description "D - LED - 0603 - Yellow (Sodium)")
      (fields (field (name "LCSC PART #") "C409441"))
      (libsource (lib "JLC_PCB") (part "19-21UYC/S530-A4/TR8"))
    )
    (comp (ref "LED_2")
      (value "19-21UYC/S530-A4/TR8")
      (footprint "D_0603")
      (description "D - LED - 0603 - Yellow (Sodium)")
      (fields (field (name "LCSC PART #") "C409441"))
      (libsource (lib "JLC_PCB") (part "19-21UYC/S530-A4/TR8"))
    )
    (comp (ref "LED_3")
      (value "19-21UYC/S530-A4/TR8")
      (footprint "D_0603")
      (description "D - LED - 0603 - Yellow (Sodium)")
      (fields (field (name "LCSC PART #") "C409441"))
      (libsource (lib "JLC_PCB") (part "19-21UYC/S530-A4/TR8"))
    )
    (comp (ref "LED_4")
      (value "19-21UYC/S530-A4/TR8")
      (footprint "D_0603")
      (description "D - LED - 0603 - Yellow (Sodium)")
      (fields (field (name "LCSC PART #") "C409441"))
      (libsource (lib "JLC_PCB") (part "19-21UYC/S530-A4/TR8"))
    )
    (comp (ref "NT_0")
      (value "0")
      (footprint "NET_TIE")
      (description "R - Net Tie")
      (libsource (lib "JLC_PCB") (part "NET_TIE"))
    )
    (comp (ref "NT_1")
      (value "0")
      (footprint "NET_TIE")
      (description "R - Net Tie")
      (libsource (lib "JLC_PCB") (part "NET_TIE"))
    )
    (comp (ref "NT_2")
      (value "0")
      (footprint "NET_TIE")
      (description "R - Net Tie")
      (libsource (lib "JLC_PCB") (part "NET_TIE"))
    )
    (comp (ref "Q10")
      (value "AO3401A")
      (footprint "TO-236AB")
      (description "Q - TRANSISTOR - MOSFET (P) - 30V - 1.4A - 0.44 Ohm")
      (fields (field (name "LCSC PART #") "C15127"))
      (libsource (lib "JLC_PCB") (part "AO3401A"))
    )
    (comp (ref "Q11")
      (value "AO3401A")
      (footprint "TO-236AB")
      (description "Q - TRANSISTOR - MOSFET (P) - 30V - 1.4A - 0.44 Ohm")
      (fields (field (name "LCSC PART #") "C15127"))
      (libsource (lib "JLC_PCB") (part "AO3401A"))
    )
    (comp (ref "Q12")
      (value "2N7002")
      (footprint "TO-236AB")
      (description "Q - TRANSISTOR - MOSFET (N) - 60V - 200mW")
      (fields (field (name "LCSC PART #") "C8545"))
      (libsource (lib "JLC_PCB") (part "2N7002"))
    )
    (comp (ref "Q13")
      (value "2N7002")
      (footprint "TO-236AB")
      (description "Q - TRANSISTOR - MOSFET (N) - 60V - 200mW")
      (fields (field (name "LCSC PART #") "C8545"))
      (libsource (lib "JLC_PCB") (part "2N7002"))
    )
    (comp (ref "Q14")
      (value "2N7002")
      (footprint "TO-236AB")
      (description "Q - TRANSISTOR - MOSFET (N) - 60V - 200mW")
      (fields (field (name "LCSC PART #") "C8545"))
      (libsource (lib "JLC_PCB") (part "2N7002"))
    )
    (comp (ref "Q15")
      (value "AO3401A")
      (footprint "TO-236AB")
      (description "Q - TRANSISTOR - MOSFET (P) - 30V - 1.4A - 0.44 Ohm")
      (fields (field (name "LCSC PART #") "C15127"))
      (libsource (lib "JLC_PCB") (part "AO3401A"))
    )
    (comp (ref "Q18")
      (value "2N7002")
      (footprint "TO-236AB")
      (description "Q - TRANSISTOR - MOSFET (N) - 60V - 200mW")
      (fields (field (name "LCSC PART #") "C8545"))
      (libsource (lib "JLC_PCB") (part "2N7002"))
    )
    (comp (ref "Q19")
      (value "AO3401A")
      (footprint "TO-236AB")
      (description "Q - TRANSISTOR - MOSFET (P) - 30V - 1.4A - 0.44 Ohm")
      (fields (field (name "LCSC PART #") "C15127"))
      (libsource (lib "JLC_PCB") (part "AO3401A"))
    )
    (comp (ref "QBD_1A")
      (value "NCE60P12K")
      (footprint "TO-252AA")
      (description "Q - TRANSISTOR - MOSFET (P) - 60V - 12A - 0.1R")
      (fields (field (name "LCSC PART #") "C326372"))
      (libsource (lib "JLC_PCB") (part "NCE60P12K"))
    )
    (comp (ref "QBD_1B")
      (value "NCE60P12K")
      (footprint "TO-252AA")
      (description "Q - TRANSISTOR - MOSFET (P) - 60V - 12A - 0.1R")
      (fields (field (name "LCSC PART #") "C326372"))
      (libsource (lib "JLC_PCB") (part "NCE60P12K"))
    )
    (comp (ref "QBD_2A")
      (value "NCE60P12K")
      (footprint "TO-252AA")
      (description "Q - TRANSISTOR - MOSFET (P) - 60V - 12A - 0.1R")
      (fields (field (name "LCSC PART #") "C326372"))
      (libsource (lib "JLC_PCB") (part "NCE60P12K"))
    )
    (comp (ref "QBD_2B")
      (value "NCE60P12K")
      (footprint "TO-252AA")
      (description "Q - TRANSISTOR - MOSFET (P) - 60V - 12A - 0.1R")
      (fields (field (name "LCSC PART #") "C326372"))
      (libsource (lib "JLC_PCB") (part "NCE60P12K"))
    )
    (comp (ref "QBD_3A")
      (value "NCE60P12K")
      (footprint "TO-252AA")
      (description "Q - TRANSISTOR - MOSFET (P) - 60V - 12A - 0.1R")
      (fields (field (name "LCSC PART #") "C326372"))
      (libsource (lib "JLC_PCB") (part "NCE60P12K"))
    )
    (comp (ref "QBD_3B")
      (value "NCE60P12K")
      (footprint "TO-252AA")
      (description "Q - TRANSISTOR - MOSFET (P) - 60V - 12A - 0.1R")
      (fields (field (name "LCSC PART #") "C326372"))
      (libsource (lib "JLC_PCB") (part "NCE60P12K"))
    )
    (comp (ref "QBD_4A")
      (value "NCE60P12K")
      (footprint "TO-252AA")
      (description "Q - TRANSISTOR - MOSFET (P) - 60V - 12A - 0.1R")
      (fields (field (name "LCSC PART #") "C326372"))
      (libsource (lib "JLC_PCB") (part "NCE60P12K"))
    )
    (comp (ref "QBD_4B")
      (value "NCE60P12K")
      (footprint "TO-252AA")
      (description "Q - TRANSISTOR - MOSFET (P) - 60V - 12A - 0.1R")
      (fields (field (name "LCSC PART #") "C326372"))
      (libsource (lib "JLC_PCB") (part "NCE60P12K"))
    )
    (comp (ref "QBD_5A")
      (value "NCE60P12K")
      (footprint "TO-252AA")
      (description "Q - TRANSISTOR - MOSFET (P) - 60V - 12A - 0.1R")
      (fields (field (name "LCSC PART #") "C326372"))
      (libsource (lib "JLC_PCB") (part "NCE60P12K"))
    )
    (comp (ref "QBD_5B")
      (value "NCE60P12K")
      (footprint "TO-252AA")
      (description "Q - TRANSISTOR - MOSFET (P) - 60V - 12A - 0.1R")
      (fields (field (name "LCSC PART #") "C326372"))
      (libsource (lib "JLC_PCB") (part "NCE60P12K"))
    )
    (comp (ref "QBEN")
      (value "2N7002")
      (footprint "TO-236AB")
      (description "Q - TRANSISTOR - MOSFET (N) - 60V - 200mW")
      (fields (field (name "LCSC PART #") "C8545"))
      (libsource (lib "JLC_PCB") (part "2N7002"))
    )
    (comp (ref "QBENR")
      (value "10k")
      (footprint "R_0402")
      (description "R - RESISTOR - SMD - 10k - 1% - 0402")
      (fields (field (name "LCSC PART #") "C25744") (field (name "Comment") "0402WGF1002TCE"))
      (libsource (lib "JLC_PCB") (part "0402WGF1002TCE"))
    )
    (comp (ref "QSHUNT")
      (value "2N7002")
      (footprint "TO-236AB")
      (description "Q - TRANSISTOR - MOSFET (N) - 60V - 200mW")
      (fields (field (name "LCSC PART #") "C8545"))
      (libsource (lib "JLC_PCB") (part "2N7002"))
    )
    (comp (ref "Q_3V3")
      (value "AO3401A")
      (footprint "TO-236AB")
      (description "Q - TRANSISTOR - MOSFET (P) - 30V - 1.4A - 0.44 Ohm")
      (fields (field (name "LCSC PART #") "C15127"))
      (libsource (lib "JLC_PCB") (part "AO3401A"))
    )
    (comp (ref "R2")
      (value "100R")
      (footprint "R_0402")
      (description "R - RESISTOR - SMD - 100R - 1% - 0402")
      (fields (field (name "LCSC PART #") "C25076") (field (name "Comment") "0402WGF1000TCE"))
      (libsource (lib "JLC_PCB") (part "0402WGF1000TCE"))
    )
    (comp (ref "R10")
      (value "1M")
      (footprint "R_0402")
      (description "R - RESISTOR - SMD - 1M - 1% - 0402")
      (fields (field (name "LCSC PART #") "C26083") (field (name "Comment") "0402WGF1004TCE"))
      (libsource (lib "JLC_PCB") (part "0402WGF1004TCE"))
    )
    (comp (ref "R11")
      (value "10k")
      (footprint "R_0402")
      (description "R - RESISTOR - SMD - 10k - 1% - 0402")
      (fields (field (name "LCSC PART #") "C25744") (field (name "Comment") "0402WGF1002TCE"))
      (libsource (lib "JLC_PCB") (part "0402WGF1002TCE"))
    )
    (comp (ref "R18")
      (value "10k")
      (footprint "R_0402")
      (description "R - RESISTOR - SMD - 10k - 1% - 0402")
      (fields (field (name "LCSC PART #") "C25744") (field (name "Comment") "0402WGF1002TCE"))
      (libsource (lib "JLC_PCB") (part "0402WGF1002TCE"))
    )
    (comp (ref "R100")
      (value "22R")
      (footprint "R_0402")
      (description "R - RESISTOR - SMD - 22R - 1% - 0402")
      (fields (field (name "LCSC PART #") "C25092") (field (name "Comment") "0402WGF220JTCE"))
      (libsource (lib "JLC_PCB") (part "0402WGF220JTCE"))
    )
    (comp (ref "R101")
      (value "22R")
      (footprint "R_0402")
      (description "R - RESISTOR - SMD - 22R - 1% - 0402")
      (fields (field (name "LCSC PART #") "C25092") (field (name "Comment") "0402WGF220JTCE"))
      (libsource (lib "JLC_PCB") (part "0402WGF220JTCE"))
    )
    (comp (ref "R102")
      (value "0R")
      (footprint "R_0402")
      (description "R - RESISTOR - SMD - 0R - 1% - 0402")
      (fields (field (name "LCSC PART #") "C17168") (field (name "Comment") "0402WGF0000TCE"))
      (libsource (lib "JLC_PCB") (part "0402WGF0000TCE"))
    )
    (comp (ref "R106")
      (value "1.5k")
      (footprint "R_0402")
      (description "R - RESISTOR - SMD - 1.5k - 1% - 0402")
      (fields (field (name "LCSC PART #") "C25867") (field (name "Comment") "0402WGF1501TCE"))
      (libsource (lib "JLC_PCB") (part "0402WGF1501TCE"))
    )
    (comp (ref "R108")
      (value "5.1k")
      (footprint "R_0402")
      (description "R - RESISTOR - SMD - 5.1k - 1% - 0402")
      (fields (field (name "LCSC PART #") "C25905") (field (name "Comment") "0402WGF5101TCE"))
      (libsource (lib "JLC_PCB") (part "0402WGF5101TCE"))
    )
    (comp (ref "R109")
      (value "5.1k")
      (footprint "R_0402")
      (description "R - RESISTOR - SMD - 5.1k - 1% - 0402")
      (fields (field (name "LCSC PART #") "C25905") (field (name "Comment") "0402WGF5101TCE"))
      (libsource (lib "JLC_PCB") (part "0402WGF5101TCE"))
    )
    (comp (ref "R110")
      (value "1k")
      (footprint "R_0402")
      (description "R - RESISTOR - SMD - 1k - 1% - 0402")
      (fields (field (name "LCSC PART #") "C11702") (field (name "Comment") "0402WGF1001TCE"))
      (libsource (lib "JLC_PCB") (part "0402WGF1001TCE"))
    )
    (comp (ref "RBEN")
      (value "100R")
      (footprint "R_0402")
      (description "R - RESISTOR - SMD - 100R - 1% - 0402")
      (fields (field (name "LCSC PART #") "C25076") (field (name "Comment") "0402WGF1000TCE"))
      (libsource (lib "JLC_PCB") (part "0402WGF1000TCE"))
    )
    (comp (ref "RBUS_1")
      (value "10k")
      (footprint "R_0402")
      (description "R - RESISTOR - SMD - 10k - 1% - 0402")
      (fields (field (name "LCSC PART #") "C25744") (field (name "Comment") "0402WGF1002TCE"))
      (libsource (lib "JLC_PCB") (part "0402WGF1002TCE"))
    )
    (comp (ref "RBUS_2")
      (value "10k")
      (footprint "R_0402")
      (description "R - RESISTOR - SMD - 10k - 1% - 0402")
      (fields (field (name "LCSC PART #") "C25744") (field (name "Comment") "0402WGF1002TCE"))
      (libsource (lib "JLC_PCB") (part "0402WGF1002TCE"))
    )
    (comp (ref "RBUS_3")
      (value "1k")
      (footprint "R_0402")
      (description "R - RESISTOR - SMD - 1k - 1% - 0402")
      (fields (field (name "LCSC PART #") "C11702") (field (name "Comment") "0402WGF1001TCE"))
      (libsource (lib "JLC_PCB") (part "0402WGF1001TCE"))
    )
    (comp (ref "RC0")
      (value "1k")
      (footprint "R_0402")
      (description "R - RESISTOR - SMD - 1k - 1% - 0402")
      (fields (field (name "LCSC PART #") "C11702") (field (name "Comment") "0402WGF1001TCE"))
      (libsource (lib "JLC_PCB") (part "0402WGF1001TCE"))
    )
    (comp (ref "RC1")
      (value "1k")
      (footprint "R_0402")
      (description "R - RESISTOR - SMD - 1k - 1% - 0402")
      (fields (field (name "LCSC PART #") "C11702") (field (name "Comment") "0402WGF1001TCE"))
      (libsource (lib "JLC_PCB") (part "0402WGF1001TCE"))
    )
    (comp (ref "RC2")
      (value "1k")
      (footprint "R_0402")
      (description "R - RESISTOR - SMD - 1k - 1% - 0402")
      (fields (field (name "LCSC PART #") "C11702") (field (name "Comment") "0402WGF1001TCE"))
      (libsource (lib "JLC_PCB") (part "0402WGF1001TCE"))
    )
    (comp (ref "RC3")
      (value "1k")
      (footprint "R_0402")
      (description "R - RESISTOR - SMD - 1k - 1% - 0402")
      (fields (field (name "LCSC PART #") "C11702") (field (name "Comment") "0402WGF1001TCE"))
      (libsource (lib "JLC_PCB") (part "0402WGF1001TCE"))
    )
    (comp (ref "RC4")
      (value "1k")
      (footprint "R_0402")
      (description "R - RESISTOR - SMD - 1k - 1% - 0402")
      (fields (field (name "LCSC PART #") "C11702") (field (name "Comment") "0402WGF1001TCE"))
      (libsource (lib "JLC_PCB") (part "0402WGF1001TCE"))
    )
    (comp (ref "RC5A")
      (value "1k")
      (footprint "R_0402")
      (description "R - RESISTOR - SMD - 1k - 1% - 0402")
      (fields (field (name "LCSC PART #") "C11702") (field (name "Comment") "0402WGF1001TCE"))
      (libsource (lib "JLC_PCB") (part "0402WGF1001TCE"))
    )
    (comp (ref "RC5B")
      (value "1k")
      (footprint "R_0402")
      (description "R - RESISTOR - SMD - 1k - 1% - 0402")
      (fields (field (name "LCSC PART #") "C11702") (field (name "Comment") "0402WGF1001TCE"))
      (libsource (lib "JLC_PCB") (part "0402WGF1001TCE"))
    )
    (comp (ref "RC6")
      (value "1k")
      (footprint "R_0402")
      (description "R - RESISTOR - SMD - 1k - 1% - 0402")
      (fields (field (name "LCSC PART #") "C11702") (field (name "Comment") "0402WGF1001TCE"))
      (libsource (lib "JLC_PCB") (part "0402WGF1001TCE"))
    )
    (comp (ref "RC7")
      (value "1k")
      (footprint "R_0402")
      (description "R - RESISTOR - SMD - 1k - 1% - 0402")
      (fields (field (name "LCSC PART #") "C11702") (field (name "Comment") "0402WGF1001TCE"))
      (libsource (lib "JLC_PCB") (part "0402WGF1001TCE"))
    )
    (comp (ref "RC8")
      (value "1k")
      (footprint "R_0402")
      (description "R - RESISTOR - SMD - 1k - 1% - 0402")
      (fields (field (name "LCSC PART #") "C11702") (field (name "Comment") "0402WGF1001TCE"))
      (libsource (lib "JLC_PCB") (part "0402WGF1001TCE"))
    )
    (comp (ref "RC9")
      (value "1k")
      (footprint "R_0402")
      (description "R - RESISTOR - SMD - 1k - 1% - 0402")
      (fields (field (name "LCSC PART #") "C11702") (field (name "Comment") "0402WGF1001TCE"))
      (libsource (lib "JLC_PCB") (part "0402WGF1001TCE"))
    )
    (comp (ref "RC10A")
      (value "1k")
      (footprint "R_0402")
      (description "R - RESISTOR - SMD - 1k - 1% - 0402")
      (fields (field (name "LCSC PART #") "C11702") (field (name "Comment") "0402WGF1001TCE"))
      (libsource (lib "JLC_PCB") (part "0402WGF1001TCE"))
    )
    (comp (ref "RC10B")
      (value "1k")
      (footprint "R_0402")
      (description "R - RESISTOR - SMD - 1k - 1% - 0402")
      (fields (field (name "LCSC PART #") "C11702") (field (name "Comment") "0402WGF1001TCE"))
      (libsource (lib "JLC_PCB") (part "0402WGF1001TCE"))
    )
    (comp (ref "RC11")
      (value "1k")
      (footprint "R_0402")
      (description "R - RESISTOR - SMD - 1k - 1% - 0402")
      (fields (field (name "LCSC PART #") "C11702") (field (name "Comment") "0402WGF1001TCE"))
      (libsource (lib "JLC_PCB") (part "0402WGF1001TCE"))
    )
    (comp (ref "RC12")
      (value "1k")
      (footprint "R_0402")
      (description "R - RESISTOR - SMD - 1k - 1% - 0402")
      (fields (field (name "LCSC PART #") "C11702") (field (name "Comment") "0402WGF1001TCE"))
      (libsource (lib "JLC_PCB") (part "0402WGF1001TCE"))
    )
    (comp (ref "RC13")
      (value "1k")
      (footprint "R_0402")
      (description "R - RESISTOR - SMD - 1k - 1% - 0402")
      (fields (field (name "LCSC PART #") "C11702") (field (name "Comment") "0402WGF1001TCE"))
      (libsource (lib "JLC_PCB") (part "0402WGF1001TCE"))
    )
    (comp (ref "RC14")
      (value "1k")
      (footprint "R_0402")
      (description "R - RESISTOR - SMD - 1k - 1% - 0402")
      (fields (field (name "LCSC PART #") "C11702") (field (name "Comment") "0402WGF1001TCE"))
      (libsource (lib "JLC_PCB") (part "0402WGF1001TCE"))
    )
    (comp (ref "RLED_1")
      (value "1k")
      (footprint "R_0402")
      (description "R - RESISTOR - SMD - 1k - 1% - 0402")
      (fields (field (name "LCSC PART #") "C11702") (field (name "Comment") "0402WGF1001TCE"))
      (libsource (lib "JLC_PCB") (part "0402WGF1001TCE"))
    )
    (comp (ref "RLED_2")
      (value "1k")
      (footprint "R_0402")
      (description "R - RESISTOR - SMD - 1k - 1% - 0402")
      (fields (field (name "LCSC PART #") "C11702") (field (name "Comment") "0402WGF1001TCE"))
      (libsource (lib "JLC_PCB") (part "0402WGF1001TCE"))
    )
    (comp (ref "RLED_3")
      (value "1k")
      (footprint "R_0402")
      (description "R - RESISTOR - SMD - 1k - 1% - 0402")
      (fields (field (name "LCSC PART #") "C11702") (field (name "Comment") "0402WGF1001TCE"))
      (libsource (lib "JLC_PCB") (part "0402WGF1001TCE"))
    )
    (comp (ref "RLED_4")
      (value "1k")
      (footprint "R_0402")
      (description "R - RESISTOR - SMD - 1k - 1% - 0402")
      (fields (field (name "LCSC PART #") "C11702") (field (name "Comment") "0402WGF1001TCE"))
      (libsource (lib "JLC_PCB") (part "0402WGF1001TCE"))
    )
    (comp (ref "RSCL")
      (value "10k")
      (footprint "R_0402")
      (description "R - RESISTOR - SMD - 10k - 1% - 0402")
      (fields (field (name "LCSC PART #") "C25744") (field (name "Comment") "0402WGF1002TCE"))
      (libsource (lib "JLC_PCB") (part "0402WGF1002TCE"))
    )
    (comp (ref "RSDA")
      (value "10k")
      (footprint "R_0402")
      (description "R - RESISTOR - SMD - 10k - 1% - 0402")
      (fields (field (name "LCSC PART #") "C25744") (field (name "Comment") "0402WGF1002TCE"))
      (libsource (lib "JLC_PCB") (part "0402WGF1002TCE"))
    )
    (comp (ref "RSHUNT")
      (value "100k")
      (footprint "R_0402")
      (description "R - RESISTOR - SMD - 100k - 1% -  0402")
      (fields (field (name "LCSC PART #") "C25741") (field (name "Comment") "0402WGF1003TCE"))
      (libsource (lib "JLC_PCB") (part "0402WGF1003TCE"))
    )
    (comp (ref "RSHUNT2")
      (value "100k")
      (footprint "R_0402")
      (description "R - RESISTOR - SMD - 100k - 1% -  0402")
      (fields (field (name "LCSC PART #") "C25741") (field (name "Comment") "0402WGF1003TCE"))
      (libsource (lib "JLC_PCB") (part "0402WGF1003TCE"))
    )
    (comp (ref "RSHUNT3")
      (value "100R")
      (footprint "R_0402")
      (description "R - RESISTOR - SMD - 100R - 1% - 0402")
      (fields (field (name "LCSC PART #") "C25076") (field (name "Comment") "0402WGF1000TCE"))
      (libsource (lib "JLC_PCB") (part "0402WGF1000TCE"))
    )
    (comp (ref "RSNS")
      (value "1m")
      (footprint "R_2512")
      (description "R - RESISTOR - SMD - 0.001R - 1% - 2512 - 2W")
      (fields (field (name "LCSC PART #") "C76233") (field (name "POWER") "2W"))
      (libsource (lib "JLC_PCB") (part "MRF6432(2512)LR001FTS"))
    )
    (comp (ref "RSNSN")
      (value "100R")
      (footprint "R_0402")
      (description "R - RESISTOR - SMD - 100R - 1% - 0402")
      (fields (field (name "LCSC PART #") "C25076") (field (name "Comment") "0402WGF1000TCE"))
      (libsource (lib "JLC_PCB") (part "0402WGF1000TCE"))
    )
    (comp (ref "RSNSP")
      (value "100R")
      (footprint "R_0402")
      (description "R - RESISTOR - SMD - 100R - 1% - 0402")
      (fields (field (name "LCSC PART #") "C25076") (field (name "Comment") "0402WGF1000TCE"))
      (libsource (lib "JLC_PCB") (part "0402WGF1000TCE"))
    )
    (comp (ref "RS_0")
      (value "1k")
      (footprint "R_0402")
      (description "R - RESISTOR - SMD - 1k - 1% - 0402")
      (fields (field (name "LCSC PART #") "C11702") (field (name "Comment") "0402WGF1001TCE"))
      (libsource (lib "JLC_PCB") (part "0402WGF1001TCE"))
    )
    (comp (ref "RS_1")
      (value "1k")
      (footprint "R_0402")
      (description "R - RESISTOR - SMD - 1k - 1% - 0402")
      (fields (field (name "LCSC PART #") "C11702") (field (name "Comment") "0402WGF1001TCE"))
      (libsource (lib "JLC_PCB") (part "0402WGF1001TCE"))
    )
    (comp (ref "RS_2")
      (value "1k")
      (footprint "R_0402")
      (description "R - RESISTOR - SMD - 1k - 1% - 0402")
      (fields (field (name "LCSC PART #") "C11702") (field (name "Comment") "0402WGF1001TCE"))
      (libsource (lib "JLC_PCB") (part "0402WGF1001TCE"))
    )
    (comp (ref "RS_3")
      (value "1k")
      (footprint "R_0402")
      (description "R - RESISTOR - SMD - 1k - 1% - 0402")
      (fields (field (name "LCSC PART #") "C11702") (field (name "Comment") "0402WGF1001TCE"))
      (libsource (lib "JLC_PCB") (part "0402WGF1001TCE"))
    )
    (comp (ref "RS_4")
      (value "1k")
      (footprint "R_0402")
      (description "R - RESISTOR - SMD - 1k - 1% - 0402")
      (fields (field (name "LCSC PART #") "C11702") (field (name "Comment") "0402WGF1001TCE"))
      (libsource (lib "JLC_PCB") (part "0402WGF1001TCE"))
    )
    (comp (ref "RS_5")
      (value "1k")
      (footprint "R_0402")
      (description "R - RESISTOR - SMD - 1k - 1% - 0402")
      (fields (field (name "LCSC PART #") "C11702") (field (name "Comment") "0402WGF1001TCE"))
      (libsource (lib "JLC_PCB") (part "0402WGF1001TCE"))
    )
    (comp (ref "RS_6")
      (value "1k")
      (footprint "R_0402")
      (description "R - RESISTOR - SMD - 1k - 1% - 0402")
      (fields (field (name "LCSC PART #") "C11702") (field (name "Comment") "0402WGF1001TCE"))
      (libsource (lib "JLC_PCB") (part "0402WGF1001TCE"))
    )
    (comp (ref "RS_7")
      (value "1k")
      (footprint "R_0402")
      (description "R - RESISTOR - SMD - 1k - 1% - 0402")
      (fields (field (name "LCSC PART #") "C11702") (field (name "Comment") "0402WGF1001TCE"))
      (libsource (lib "JLC_PCB") (part "0402WGF1001TCE"))
    )
    (comp (ref "RS_8")
      (value "1k")
      (footprint "R_0402")
      (description "R - RESISTOR - SMD - 1k - 1% - 0402")
      (fields (field (name "LCSC PART #") "C11702") (field (name "Comment") "0402WGF1001TCE"))
      (libsource (lib "JLC_PCB") (part "0402WGF1001TCE"))
    )
    (comp (ref "RS_9")
      (value "1k")
      (footprint "R_0402")
      (description "R - RESISTOR - SMD - 1k - 1% - 0402")
      (fields (field (name "LCSC PART #") "C11702") (field (name "Comment") "0402WGF1001TCE"))
      (libsource (lib "JLC_PCB") (part "0402WGF1001TCE"))
    )
    (comp (ref "RS_10")
      (value "1k")
      (footprint "R_0402")
      (description "R - RESISTOR - SMD - 1k - 1% - 0402")
      (fields (field (name "LCSC PART #") "C11702") (field (name "Comment") "0402WGF1001TCE"))
      (libsource (lib "JLC_PCB") (part "0402WGF1001TCE"))
    )
    (comp (ref "RS_11")
      (value "1k")
      (footprint "R_0402")
      (description "R - RESISTOR - SMD - 1k - 1% - 0402")
      (fields (field (name "LCSC PART #") "C11702") (field (name "Comment") "0402WGF1001TCE"))
      (libsource (lib "JLC_PCB") (part "0402WGF1001TCE"))
    )
    (comp (ref "RS_12")
      (value "1k")
      (footprint "R_0402")
      (description "R - RESISTOR - SMD - 1k - 1% - 0402")
      (fields (field (name "LCSC PART #") "C11702") (field (name "Comment") "0402WGF1001TCE"))
      (libsource (lib "JLC_PCB") (part "0402WGF1001TCE"))
    )
    (comp (ref "RS_13")
      (value "1k")
      (footprint "R_0402")
      (description "R - RESISTOR - SMD - 1k - 1% - 0402")
      (fields (field (name "LCSC PART #") "C11702") (field (name "Comment") "0402WGF1001TCE"))
      (libsource (lib "JLC_PCB") (part "0402WGF1001TCE"))
    )
    (comp (ref "RS_14")
      (value "1k")
      (footprint "R_0402")
      (description "R - RESISTOR - SMD - 1k - 1% - 0402")
      (fields (field (name "LCSC PART #") "C11702") (field (name "Comment") "0402WGF1001TCE"))
      (libsource (lib "JLC_PCB") (part "0402WGF1001TCE"))
    )
    (comp (ref "RS_15")
      (value "1k")
      (footprint "R_0402")
      (description "R - RESISTOR - SMD - 1k - 1% - 0402")
      (fields (field (name "LCSC PART #") "C11702") (field (name "Comment") "0402WGF1001TCE"))
      (libsource (lib "JLC_PCB") (part "0402WGF1001TCE"))
    )
    (comp (ref "RS_16")
      (value "1k")
      (footprint "R_0402")
      (description "R - RESISTOR - SMD - 1k - 1% - 0402")
      (fields (field (name "LCSC PART #") "C11702") (field (name "Comment") "0402WGF1001TCE"))
      (libsource (lib "JLC_PCB") (part "0402WGF1001TCE"))
    )
    (comp (ref "RS_17")
      (value "1k")
      (footprint "R_0402")
      (description "R - RESISTOR - SMD - 1k - 1% - 0402")
      (fields (field (name "LCSC PART #") "C11702") (field (name "Comment") "0402WGF1001TCE"))
      (libsource (lib "JLC_PCB") (part "0402WGF1001TCE"))
    )
    (comp (ref "RS_18")
      (value "1k")
      (footprint "R_0402")
      (description "R - RESISTOR - SMD - 1k - 1% - 0402")
      (fields (field (name "LCSC PART #") "C11702") (field (name "Comment") "0402WGF1001TCE"))
      (libsource (lib "JLC_PCB") (part "0402WGF1001TCE"))
    )
    (comp (ref "RS_19")
      (value "1k")
      (footprint "R_0402")
      (description "R - RESISTOR - SMD - 1k - 1% - 0402")
      (fields (field (name "LCSC PART #") "C11702") (field (name "Comment") "0402WGF1001TCE"))
      (libsource (lib "JLC_PCB") (part "0402WGF1001TCE"))
    )
    (comp (ref "RS_20")
      (value "1k")
      (footprint "R_0402")
      (description "R - RESISTOR - SMD - 1k - 1% - 0402")
      (fields (field (name "LCSC PART #") "C11702") (field (name "Comment") "0402WGF1001TCE"))
      (libsource (lib "JLC_PCB") (part "0402WGF1001TCE"))
    )
    (comp (ref "RS_21")
      (value "1k")
      (footprint "R_0402")
      (description "R - RESISTOR - SMD - 1k - 1% - 0402")
      (fields (field (name "LCSC PART #") "C11702") (field (name "Comment") "0402WGF1001TCE"))
      (libsource (lib "JLC_PCB") (part "0402WGF1001TCE"))
    )
    (comp (ref "RS_22")
      (value "1k")
      (footprint "R_0402")
      (description "R - RESISTOR - SMD - 1k - 1% - 0402")
      (fields (field (name "LCSC PART #") "C11702") (field (name "Comment") "0402WGF1001TCE"))
      (libsource (lib "JLC_PCB") (part "0402WGF1001TCE"))
    )
    (comp (ref "RS_23")
      (value "1k")
      (footprint "R_0402")
      (description "R - RESISTOR - SMD - 1k - 1% - 0402")
      (fields (field (name "LCSC PART #") "C11702") (field (name "Comment") "0402WGF1001TCE"))
      (libsource (lib "JLC_PCB") (part "0402WGF1001TCE"))
    )
    (comp (ref "RS_24")
      (value "1k")
      (footprint "R_0402")
      (description "R - RESISTOR - SMD - 1k - 1% - 0402")
      (fields (field (name "LCSC PART #") "C11702") (field (name "Comment") "0402WGF1001TCE"))
      (libsource (lib "JLC_PCB") (part "0402WGF1001TCE"))
    )
    (comp (ref "RS_25")
      (value "1k")
      (footprint "R_0402")
      (description "R - RESISTOR - SMD - 1k - 1% - 0402")
      (fields (field (name "LCSC PART #") "C11702") (field (name "Comment") "0402WGF1001TCE"))
      (libsource (lib "JLC_PCB") (part "0402WGF1001TCE"))
    )
    (comp (ref "RS_26")
      (value "1k")
      (footprint "R_0402")
      (description "R - RESISTOR - SMD - 1k - 1% - 0402")
      (fields (field (name "LCSC PART #") "C11702") (field (name "Comment") "0402WGF1001TCE"))
      (libsource (lib "JLC_PCB") (part "0402WGF1001TCE"))
    )
    (comp (ref "RS_27")
      (value "1k")
      (footprint "R_0402")
      (description "R - RESISTOR - SMD - 1k - 1% - 0402")
      (fields (field (name "LCSC PART #") "C11702") (field (name "Comment") "0402WGF1001TCE"))
      (libsource (lib "JLC_PCB") (part "0402WGF1001TCE"))
    )
    (comp (ref "RS_28")
      (value "1k")
      (footprint "R_0402")
      (description "R - RESISTOR - SMD - 1k - 1% - 0402")
      (fields (field (name "LCSC PART #") "C11702") (field (name "Comment") "0402WGF1001TCE"))
      (libsource (lib "JLC_PCB") (part "0402WGF1001TCE"))
    )
    (comp (ref "RS_29")
      (value "1k")
      (footprint "R_0402")
      (description "R - RESISTOR - SMD - 1k - 1% - 0402")
      (fields (field (name "LCSC PART #") "C11702") (field (name "Comment") "0402WGF1001TCE"))
      (libsource (lib "JLC_PCB") (part "0402WGF1001TCE"))
    )
    (comp (ref "RTS2")
      (value "10k")
      (footprint "R_0402")
      (description "RT - NTC THERMISTOR - 10k - 1% - 0402")
      (fields (field (name "LCSC PART #") "C77131") (field (name "Comment") "NCP15XH103F03RC"))
      (libsource (lib "JLC_PCB") (part "NCP15XH103F03RC"))
    )
    (comp (ref "RT_0A")
      (value "10k")
      (footprint "R_0402")
      (description "R - RESISTOR - SMD - 10k - 1% - 0402")
      (fields (field (name "LCSC PART #") "C25744") (field (name "Comment") "0402WGF1002TCE"))
      (libsource (lib "JLC_PCB") (part "0402WGF1002TCE"))
    )
    (comp (ref "RT_0B")
      (value "10k")
      (footprint "R_0402")
      (description "R - RESISTOR - SMD - 10k - 1% - 0402")
      (fields (field (name "LCSC PART #") "C25744") (field (name "Comment") "0402WGF1002TCE"))
      (libsource (lib "JLC_PCB") (part "0402WGF1002TCE"))
    )
    (comp (ref "RT_1A")
      (value "10k")
      (footprint "R_0402")
      (description "R - RESISTOR - SMD - 10k - 1% - 0402")
      (fields (field (name "LCSC PART #") "C25744") (field (name "Comment") "0402WGF1002TCE"))
      (libsource (lib "JLC_PCB") (part "0402WGF1002TCE"))
    )
    (comp (ref "RT_1B")
      (value "10k")
      (footprint "R_0402")
      (description "R - RESISTOR - SMD - 10k - 1% - 0402")
      (fields (field (name "LCSC PART #") "C25744") (field (name "Comment") "0402WGF1002TCE"))
      (libsource (lib "JLC_PCB") (part "0402WGF1002TCE"))
    )
    (comp (ref "RT_2A")
      (value "10k")
      (footprint "R_0402")
      (description "R - RESISTOR - SMD - 10k - 1% - 0402")
      (fields (field (name "LCSC PART #") "C25744") (field (name "Comment") "0402WGF1002TCE"))
      (libsource (lib "JLC_PCB") (part "0402WGF1002TCE"))
    )
    (comp (ref "RT_2B")
      (value "10k")
      (footprint "R_0402")
      (description "R - RESISTOR - SMD - 10k - 1% - 0402")
      (fields (field (name "LCSC PART #") "C25744") (field (name "Comment") "0402WGF1002TCE"))
      (libsource (lib "JLC_PCB") (part "0402WGF1002TCE"))
    )
    (comp (ref "RT_3A")
      (value "10k")
      (footprint "R_0402")
      (description "R - RESISTOR - SMD - 10k - 1% - 0402")
      (fields (field (name "LCSC PART #") "C25744") (field (name "Comment") "0402WGF1002TCE"))
      (libsource (lib "JLC_PCB") (part "0402WGF1002TCE"))
    )
    (comp (ref "RT_3B")
      (value "10k")
      (footprint "R_0402")
      (description "R - RESISTOR - SMD - 10k - 1% - 0402")
      (fields (field (name "LCSC PART #") "C25744") (field (name "Comment") "0402WGF1002TCE"))
      (libsource (lib "JLC_PCB") (part "0402WGF1002TCE"))
    )
    (comp (ref "RT_4A")
      (value "10k")
      (footprint "R_0402")
      (description "R - RESISTOR - SMD - 10k - 1% - 0402")
      (fields (field (name "LCSC PART #") "C25744") (field (name "Comment") "0402WGF1002TCE"))
      (libsource (lib "JLC_PCB") (part "0402WGF1002TCE"))
    )
    (comp (ref "RT_4B")
      (value "10k")
      (footprint "R_0402")
      (description "R - RESISTOR - SMD - 10k - 1% - 0402")
      (fields (field (name "LCSC PART #") "C25744") (field (name "Comment") "0402WGF1002TCE"))
      (libsource (lib "JLC_PCB") (part "0402WGF1002TCE"))
    )
    (comp (ref "RT_5A")
      (value "10k")
      (footprint "R_0402")
      (description "R - RESISTOR - SMD - 10k - 1% - 0402")
      (fields (field (name "LCSC PART #") "C25744") (field (name "Comment") "0402WGF1002TCE"))
      (libsource (lib "JLC_PCB") (part "0402WGF1002TCE"))
    )
    (comp (ref "RT_5B")
      (value "10k")
      (footprint "R_0402")
      (description "R - RESISTOR - SMD - 10k - 1% - 0402")
      (fields (field (name "LCSC PART #") "C25744") (field (name "Comment") "0402WGF1002TCE"))
      (libsource (lib "JLC_PCB") (part "0402WGF1002TCE"))
    )
    (comp (ref "RT_6A")
      (value "10k")
      (footprint "R_0402")
      (description "R - RESISTOR - SMD - 10k - 1% - 0402")
      (fields (field (name "LCSC PART #") "C25744") (field (name "Comment") "0402WGF1002TCE"))
      (libsource (lib "JLC_PCB") (part "0402WGF1002TCE"))
    )
    (comp (ref "RT_6B")
      (value "10k")
      (footprint "R_0402")
      (description "R - RESISTOR - SMD - 10k - 1% - 0402")
      (fields (field (name "LCSC PART #") "C25744") (field (name "Comment") "0402WGF1002TCE"))
      (libsource (lib "JLC_PCB") (part "0402WGF1002TCE"))
    )
    (comp (ref "RT_7A")
      (value "10k")
      (footprint "R_0402")
      (description "R - RESISTOR - SMD - 10k - 1% - 0402")
      (fields (field (name "LCSC PART #") "C25744") (field (name "Comment") "0402WGF1002TCE"))
      (libsource (lib "JLC_PCB") (part "0402WGF1002TCE"))
    )
    (comp (ref "RT_7B")
      (value "10k")
      (footprint "R_0402")
      (description "R - RESISTOR - SMD - 10k - 1% - 0402")
      (fields (field (name "LCSC PART #") "C25744") (field (name "Comment") "0402WGF1002TCE"))
      (libsource (lib "JLC_PCB") (part "0402WGF1002TCE"))
    )
    (comp (ref "RT_8A")
      (value "10k")
      (footprint "R_0402")
      (description "R - RESISTOR - SMD - 10k - 1% - 0402")
      (fields (field (name "LCSC PART #") "C25744") (field (name "Comment") "0402WGF1002TCE"))
      (libsource (lib "JLC_PCB") (part "0402WGF1002TCE"))
    )
    (comp (ref "RT_8B")
      (value "10k")
      (footprint "R_0402")
      (description "R - RESISTOR - SMD - 10k - 1% - 0402")
      (fields (field (name "LCSC PART #") "C25744") (field (name "Comment") "0402WGF1002TCE"))
      (libsource (lib "JLC_PCB") (part "0402WGF1002TCE"))
    )
    (comp (ref "RT_9A")
      (value "10k")
      (footprint "R_0402")
      (description "R - RESISTOR - SMD - 10k - 1% - 0402")
      (fields (field (name "LCSC PART #") "C25744") (field (name "Comment") "0402WGF1002TCE"))
      (libsource (lib "JLC_PCB") (part "0402WGF1002TCE"))
    )
    (comp (ref "RT_9B")
      (value "10k")
      (footprint "R_0402")
      (description "R - RESISTOR - SMD - 10k - 1% - 0402")
      (fields (field (name "LCSC PART #") "C25744") (field (name "Comment") "0402WGF1002TCE"))
      (libsource (lib "JLC_PCB") (part "0402WGF1002TCE"))
    )
    (comp (ref "RT_10A")
      (value "10k")
      (footprint "R_0402")
      (description "R - RESISTOR - SMD - 10k - 1% - 0402")
      (fields (field (name "LCSC PART #") "C25744") (field (name "Comment") "0402WGF1002TCE"))
      (libsource (lib "JLC_PCB") (part "0402WGF1002TCE"))
    )
    (comp (ref "RT_10B")
      (value "10k")
      (footprint "R_0402")
      (description "R - RESISTOR - SMD - 10k - 1% - 0402")
      (fields (field (name "LCSC PART #") "C25744") (field (name "Comment") "0402WGF1002TCE"))
      (libsource (lib "JLC_PCB") (part "0402WGF1002TCE"))
    )
    (comp (ref "RT_11A")
      (value "10k")
      (footprint "R_0402")
      (description "R - RESISTOR - SMD - 10k - 1% - 0402")
      (fields (field (name "LCSC PART #") "C25744") (field (name "Comment") "0402WGF1002TCE"))
      (libsource (lib "JLC_PCB") (part "0402WGF1002TCE"))
    )
    (comp (ref "RT_11B")
      (value "10k")
      (footprint "R_0402")
      (description "R - RESISTOR - SMD - 10k - 1% - 0402")
      (fields (field (name "LCSC PART #") "C25744") (field (name "Comment") "0402WGF1002TCE"))
      (libsource (lib "JLC_PCB") (part "0402WGF1002TCE"))
    )
    (comp (ref "RT_12A")
      (value "10k")
      (footprint "R_0402")
      (description "R - RESISTOR - SMD - 10k - 1% - 0402")
      (fields (field (name "LCSC PART #") "C25744") (field (name "Comment") "0402WGF1002TCE"))
      (libsource (lib "JLC_PCB") (part "0402WGF1002TCE"))
    )
    (comp (ref "RT_12B")
      (value "10k")
      (footprint "R_0402")
      (description "R - RESISTOR - SMD - 10k - 1% - 0402")
      (fields (field (name "LCSC PART #") "C25744") (field (name "Comment") "0402WGF1002TCE"))
      (libsource (lib "JLC_PCB") (part "0402WGF1002TCE"))
    )
    (comp (ref "RT_13A")
      (value "10k")
      (footprint "R_0402")
      (description "R - RESISTOR - SMD - 10k - 1% - 0402")
      (fields (field (name "LCSC PART #") "C25744") (field (name "Comment") "0402WGF1002TCE"))
      (libsource (lib "JLC_PCB") (part "0402WGF1002TCE"))
    )
    (comp (ref "RT_13B")
      (value "10k")
      (footprint "R_0402")
      (description "R - RESISTOR - SMD - 10k - 1% - 0402")
      (fields (field (name "LCSC PART #") "C25744") (field (name "Comment") "0402WGF1002TCE"))
      (libsource (lib "JLC_PCB") (part "0402WGF1002TCE"))
    )
    (comp (ref "RT_14A")
      (value "10k")
      (footprint "R_0402")
      (description "R - RESISTOR - SMD - 10k - 1% - 0402")
      (fields (field (name "LCSC PART #") "C25744") (field (name "Comment") "0402WGF1002TCE"))
      (libsource (lib "JLC_PCB") (part "0402WGF1002TCE"))
    )
    (comp (ref "RT_14B")
      (value "10k")
      (footprint "R_0402")
      (description "R - RESISTOR - SMD - 10k - 1% - 0402")
      (fields (field (name "LCSC PART #") "C25744") (field (name "Comment") "0402WGF1002TCE"))
      (libsource (lib "JLC_PCB") (part "0402WGF1002TCE"))
    )
    (comp (ref "RT_15B")
      (value "10k")
      (footprint "R_0402")
      (description "R - RESISTOR - SMD - 10k - 1% - 0402")
      (fields (field (name "LCSC PART #") "C25744") (field (name "Comment") "0402WGF1002TCE"))
      (libsource (lib "JLC_PCB") (part "0402WGF1002TCE"))
    )
    (comp (ref "R_CMOS")
      (value "100R")
      (footprint "R_0402")
      (description "R - RESISTOR - SMD - 100R - 1% - 0402")
      (fields (field (name "LCSC PART #") "C25076") (field (name "Comment") "0402WGF1000TCE"))
      (libsource (lib "JLC_PCB") (part "0402WGF1000TCE"))
    )
    (comp (ref "SW1")
      (value "TS-1187A-C-C-B")
      (footprint "TS-1187A-C-C-B")
      (description "SW - SWITCH - SPST - NO - Top Actuated Surface Mount")
      (fields (field (name "LCSC PART #") "C318889"))
      (libsource (lib "JLC_PCB") (part "TS-1187A-C-C-B"))
    )
    (comp (ref "TSQ1a")
      (value "2N7002")
      (footprint "TO-236AB")
      (description "Q - TRANSISTOR - MOSFET (N) - 60V - 200mW")
      (fields (field (name "LCSC PART #") "C8545"))
      (libsource (lib "JLC_PCB") (part "2N7002"))
    )
    (comp (ref "TSQ1b")
      (value "2N7002")
      (footprint "TO-236AB")
      (description "Q - TRANSISTOR - MOSFET (N) - 60V - 200mW")
      (fields (field (name "LCSC PART #") "C8545"))
      (libsource (lib "JLC_PCB") (part "2N7002"))
    )
    (comp (ref "U1")
      (value "BQ7694002DBTR")
      (footprint "TSSOP50P580X150-44N")
      (description "9 to 15-series cell li-ion and li-phosphate battery monitor (bq76940 family)")
      (libsource (lib "U") (part "BQ7694002DBTR"))
    )
    (comp (ref "U2")
      (value "74HC4067PW,118")
      (footprint "SILICON:TSSOP-24-P0.65MM-W4.4MM")
      (description "U - IC -16 Port Analog MUX")
      (fields (field (name "LCSC PART #") "C179326"))
      (libsource (lib "JLC_PCB") (part "74HC4067PW,118"))
    )
    (comp (ref "U100")
      (value "GD32F103CBT6")
      (footprint "SILICON:QFP-48-P0.5MM")
      (description "U - IC - MCU, 128 KB Flash, 20 KB Internal RAM, 37 I/Os, 48-pin LQFP, -40 to 85 degC")
      (fields (field (name "LCSC PART #") "C77979"))
      (libsource (lib "JLC_PCB") (part "GD32F103CBT6"))
    )
    (comp (ref "U101")
      (value "XC6206P332MR")
      (footprint "SILICON:TO-236AB")
      (description "U - IC - LDO 3.3V 200mA")
      (fields (field (name "LCSC PART #") "C5446"))
      (libsource (lib "JLC_PCB") (part "XC6206P332MR"))
    )
    (comp (ref "Y100")
      (value "X50328MSB2GI")
      (footprint "YSX530GA")
      (description "Y - RESONATOR - 8MHZ ±10PPM - SMD-5032")
      (fields (field (name "ALTIUM_VALUE") "8MHz") (field (name "LCSC PART #") "C115962"))
      (libsource (lib "JLC_PCB") (part "X50328MSB2GI"))
    )
  )
  (nets
    (net (code "1") (name "/3V3_EN") (class "Default")
      (node (ref "3V3R2") (pin "2") (pinfunction "2_2") (pintype "passive"))
      (node (ref "U100") (pin "3") (pinfunction "PC14-OSC32_IN_3") (pintype "bidirectional"))
    )
    (net (code "2") (name "/ADDRESS_SENSE_EN") (class "Default")
      (node (ref "D_ADR_VCC") (pin "2") (pinfunction "A_2") (pintype "passive"))
      (node (ref "U100") (pin "38") (pinfunction "PA15_38") (pintype "bidirectional"))
    )
    (net (code "3") (name "/AFE_ALERT") (class "Default")
      (node (ref "U1") (pin "44") (pinfunction "ALERT_44") (pintype "passive"))
      (node (ref "U100") (pin "2") (pinfunction "PC13-TAMPER-RTC_2") (pintype "bidirectional"))
    )
    (net (code "4") (name "/AFE_SCL") (class "Default")
      (node (ref "RSCL") (pin "2") (pinfunction "2_2") (pintype "passive"))
      (node (ref "U1") (pin "5") (pinfunction "SCL_5") (pintype "passive"))
      (node (ref "U100") (pin "21") (pinfunction "PB10_21") (pintype "bidirectional"))
    )
    (net (code "5") (name "/AFE_SDA") (class "Default")
      (node (ref "RSDA") (pin "2") (pinfunction "2_2") (pintype "passive"))
      (node (ref "U1") (pin "4") (pinfunction "SDA_4") (pintype "passive"))
      (node (ref "U100") (pin "22") (pinfunction "PB11_22") (pintype "bidirectional"))
    )
    (net (code "6") (name "/AFE_WAKE") (class "Default")
      (node (ref "U1") (pin "6") (pinfunction "TS1_6") (pintype "passive"))
      (node (ref "U100") (pin "26") (pinfunction "PB13_26") (pintype "bidirectional"))
    )
    (net (code "7") (name "/A_GND") (class "Default")
      (node (ref "C105") (pin "1") (pinfunction "1_1") (pintype "passive"))
      (node (ref "CTS_15") (pin "1") (pinfunction "1_1") (pintype "passive"))
      (node (ref "NT_1") (pin "1") (pinfunction "1_1") (pintype "passive"))
      (node (ref "R102") (pin "2") (pinfunction "2_2") (pintype "passive"))
      (node (ref "RTS2") (pin "1") (pinfunction "1_1") (pintype "passive"))
      (node (ref "TSQ1a") (pin "2") (pinfunction "S_2") (pintype "passive"))
      (node (ref "TSQ1b") (pin "2") (pinfunction "S_2") (pintype "passive"))
      (node (ref "U100") (pin "8") (pinfunction "VSSA_8") (pintype "power_in"))
    )
    (net (code "8") (name "/BATT_EN") (class "Default")
      (node (ref "QBEN") (pin "1") (pinfunction "G_1") (pintype "passive"))
      (node (ref "QBENR") (pin "1") (pinfunction "1_1") (pintype "passive"))
      (node (ref "U100") (pin "14") (pinfunction "PA4_14") (pintype "bidirectional"))
    )
    (net (code "9") (name "/BB_A0") (class "Default")
      (node (ref "D_BB_0") (pin "2") (pinfunction "A_2") (pintype "passive"))
    )
    (net (code "10") (name "/BB_A1") (class "Default")
      (node (ref "D_BB_1") (pin "2") (pinfunction "A_2") (pintype "passive"))
    )
    (net (code "11") (name "/BB_A2") (class "Default")
      (node (ref "D_BB_2") (pin "2") (pinfunction "A_2") (pintype "passive"))
    )
    (net (code "12") (name "/BB_A3") (class "Default")
      (node (ref "D_BB_3") (pin "2") (pinfunction "A_2") (pintype "passive"))
    )
    (net (code "13") (name "/BB_A4") (class "Default")
      (node (ref "D_BB_4") (pin "2") (pinfunction "A_2") (pintype "passive"))
    )
    (net (code "14") (name "/BB_A5") (class "Default")
      (node (ref "D_BB_5") (pin "2") (pinfunction "A_2") (pintype "passive"))
    )
    (net (code "15") (name "/BB_A6") (class "Default")
      (node (ref "D_BB_6") (pin "2") (pinfunction "A_2") (pintype "passive"))
    )
    (net (code "16") (name "/BB_SNS") (class "Default")
      (node (ref "D_BB_VCC") (pin "1") (pinfunction "K_1") (pintype "passive"))
    )
    (net (code "17") (name "/BUSBAR_SENSE_EN") (class "Default")
      (node (ref "D_BB_VCC") (pin "2") (pinfunction "A_2") (pintype "passive"))
      (node (ref "U100") (pin "11") (pinfunction "PA1_11") (pintype "bidirectional"))
    )
    (net (code "18") (name "/B_SCL") (class "Default")
      (node (ref "U100") (pin "42") (pinfunction "PB6_42") (pintype "bidirectional"))
    )
    (net (code "19") (name "/B_SDA") (class "Default")
      (node (ref "U100") (pin "43") (pinfunction "PB7_43") (pintype "bidirectional"))
    )
    (net (code "20") (name "/C0") (class "Default")
      (node (ref "CC0A") (pin "1") (pinfunction "1_1") (pintype "passive"))
      (node (ref "NT_0") (pin "1") (pinfunction "1_1") (pintype "passive"))
      (node (ref "RC0") (pin "2") (pinfunction "2_2") (pintype "passive"))
    )
    (net (code "21") (name "/C1") (class "Default")
      (node (ref "CC0B") (pin "2") (pinfunction "2_2") (pintype "passive"))
      (node (ref "CC1") (pin "1") (pinfunction "1_1") (pintype "passive"))
      (node (ref "RC1") (pin "2") (pinfunction "2_2") (pintype "passive"))
    )
    (net (code "22") (name "/C2") (class "Default")
      (node (ref "CC1") (pin "2") (pinfunction "2_2") (pintype "passive"))
      (node (ref "CC2") (pin "1") (pinfunction "1_1") (pintype "passive"))
      (node (ref "RC2") (pin "2") (pinfunction "2_2") (pintype "passive"))
    )
    (net (code "23") (name "/C3") (class "Default")
      (node (ref "CC2") (pin "2") (pinfunction "2_2") (pintype "passive"))
      (node (ref "CC3") (pin "1") (pinfunction "1_1") (pintype "passive"))
      (node (ref "RC3") (pin "2") (pinfunction "2_2") (pintype "passive"))
    )
    (net (code "24") (name "/C4") (class "Default")
      (node (ref "CC3") (pin "2") (pinfunction "2_2") (pintype "passive"))
      (node (ref "CC4") (pin "1") (pinfunction "1_1") (pintype "passive"))
      (node (ref "RC4") (pin "2") (pinfunction "2_2") (pintype "passive"))
    )
    (net (code "25") (name "/C5") (class "Default")
      (node (ref "CC4") (pin "2") (pinfunction "2_2") (pintype "passive"))
      (node (ref "CC5A") (pin "1") (pinfunction "1_1") (pintype "passive"))
      (node (ref "RC5A") (pin "2") (pinfunction "2_2") (pintype "passive"))
      (node (ref "RC5B") (pin "2") (pinfunction "2_2") (pintype "passive"))
    )
    (net (code "26") (name "/C6") (class "Default")
      (node (ref "CC5B") (pin "2") (pinfunction "2_2") (pintype "passive"))
      (node (ref "CC6") (pin "1") (pinfunction "1_1") (pintype "passive"))
      (node (ref "RC6") (pin "2") (pinfunction "2_2") (pintype "passive"))
    )
    (net (code "27") (name "/C7") (class "Default")
      (node (ref "CC6") (pin "2") (pinfunction "2_2") (pintype "passive"))
      (node (ref "CC7") (pin "1") (pinfunction "1_1") (pintype "passive"))
      (node (ref "RC7") (pin "2") (pinfunction "2_2") (pintype "passive"))
    )
    (net (code "28") (name "/C8") (class "Default")
      (node (ref "CC7") (pin "2") (pinfunction "2_2") (pintype "passive"))
      (node (ref "CC8") (pin "1") (pinfunction "1_1") (pintype "passive"))
      (node (ref "RC8") (pin "2") (pinfunction "2_2") (pintype "passive"))
    )
    (net (code "29") (name "/C9") (class "Default")
      (node (ref "CC8") (pin "2") (pinfunction "2_2") (pintype "passive"))
      (node (ref "CC9") (pin "1") (pinfunction "1_1") (pintype "passive"))
      (node (ref "RC9") (pin "2") (pinfunction "2_2") (pintype "passive"))
    )
    (net (code "30") (name "/C10") (class "Default")
      (node (ref "CC10A") (pin "1") (pinfunction "1_1") (pintype "passive"))
      (node (ref "CC9") (pin "2") (pinfunction "2_2") (pintype "passive"))
      (node (ref "RC10A") (pin "2") (pinfunction "2_2") (pintype "passive"))
      (node (ref "RC10B") (pin "2") (pinfunction "2_2") (pintype "passive"))
    )
    (net (code "31") (name "/C11") (class "Default")
      (node (ref "CC10B") (pin "2") (pinfunction "2_2") (pintype "passive"))
      (node (ref "CC11") (pin "1") (pinfunction "1_1") (pintype "passive"))
      (node (ref "RC11") (pin "2") (pinfunction "2_2") (pintype "passive"))
    )
    (net (code "32") (name "/C12") (class "Default")
      (node (ref "CC11") (pin "2") (pinfunction "2_2") (pintype "passive"))
      (node (ref "CC12") (pin "1") (pinfunction "1_1") (pintype "passive"))
      (node (ref "RC12") (pin "2") (pinfunction "2_2") (pintype "passive"))
    )
    (net (code "33") (name "/C13") (class "Default")
      (node (ref "CC12") (pin "2") (pinfunction "2_2") (pintype "passive"))
      (node (ref "CC13") (pin "1") (pinfunction "1_1") (pintype "passive"))
      (node (ref "RC13") (pin "2") (pinfunction "2_2") (pintype "passive"))
    )
    (net (code "34") (name "/C14") (class "Default")
      (node (ref "CC13") (pin "2") (pinfunction "2_2") (pintype "passive"))
      (node (ref "CC14") (pin "1") (pinfunction "1_1") (pintype "passive"))
      (node (ref "RC14") (pin "2") (pinfunction "2_2") (pintype "passive"))
    )
    (net (code "35") (name "/C15") (class "Default")
      (node (ref "CC14") (pin "2") (pinfunction "2_2") (pintype "passive"))
      (node (ref "CC15") (pin "2") (pinfunction "2_2") (pintype "passive"))
      (node (ref "DS_1") (pin "1") (pinfunction "K_1") (pintype "passive"))
      (node (ref "QBD_1B") (pin "2") (pinfunction "D_2") (pintype "passive"))
      (node (ref "QBD_2B") (pin "2") (pinfunction "D_2") (pintype "passive"))
      (node (ref "QBD_3B") (pin "2") (pinfunction "D_2") (pintype "passive"))
      (node (ref "QBD_4B") (pin "2") (pinfunction "D_2") (pintype "passive"))
      (node (ref "QBD_5B") (pin "2") (pinfunction "D_2") (pintype "passive"))
      (node (ref "QSHUNT") (pin "3") (pinfunction "D_3") (pintype "passive"))
    )
    (net (code "36") (name "/CC1") (class "Default")
      (node (ref "J100") (pin "A5") (pinfunction "CC1_A5") (pintype "passive"))
      (node (ref "R108") (pin "2") (pinfunction "2_2") (pintype "passive"))
    )
    (net (code "37") (name "/CC2") (class "Default")
      (node (ref "J100") (pin "B5") (pinfunction "CC2_B5") (pintype "passive"))
      (node (ref "R109") (pin "2") (pinfunction "2_2") (pintype "passive"))
    )
    (net (code "38") (name "/CHIP_SELECT") (class "Default")
      (node (ref "U100") (pin "25") (pinfunction "PB12_25") (pintype "bidirectional"))
    )
    (net (code "39") (name "/COS") (class "Default")
      (node (ref "U100") (pin "16") (pinfunction "PA6_16") (pintype "bidirectional"))
    )
    (net (code "40") (name "/DATA_BUS_A0") (class "Default")
      (node (ref "D_ADR_0") (pin "1") (pinfunction "K_1") (pintype "passive"))
      (node (ref "D_BB_0") (pin "1") (pinfunction "K_1") (pintype "passive"))
      (node (ref "U100") (pin "40") (pinfunction "PB4_40") (pintype "bidirectional"))
      (node (ref "U2") (pin "10") (pinfunction "S0_10") (pintype "passive"))
    )
    (net (code "41") (name "/DATA_BUS_A1") (class "Default")
      (node (ref "D_ADR_1") (pin "1") (pinfunction "K_1") (pintype "passive"))
      (node (ref "D_BB_1") (pin "1") (pinfunction "K_1") (pintype "passive"))
      (node (ref "U100") (pin "41") (pinfunction "PB5_41") (pintype "bidirectional"))
      (node (ref "U2") (pin "11") (pinfunction "S1_11") (pintype "passive"))
    )
    (net (code "42") (name "/DATA_BUS_A2") (class "Default")
      (node (ref "D_ADR_2") (pin "1") (pinfunction "K_1") (pintype "passive"))
      (node (ref "D_BB_2") (pin "1") (pinfunction "K_1") (pintype "passive"))
      (node (ref "U100") (pin "31") (pinfunction "PA10_31") (pintype "bidirectional"))
      (node (ref "U2") (pin "14") (pinfunction "S2_14") (pintype "passive"))
    )
    (net (code "43") (name "/DATA_BUS_A3") (class "Default")
      (node (ref "D_ADR_3") (pin "1") (pinfunction "K_1") (pintype "passive"))
      (node (ref "D_BB_3") (pin "1") (pinfunction "K_1") (pintype "passive"))
      (node (ref "U100") (pin "30") (pinfunction "PA9_30") (pintype "bidirectional"))
      (node (ref "U2") (pin "13") (pinfunction "S3_13") (pintype "passive"))
    )
    (net (code "44") (name "/DATA_BUS_A4") (class "Default")
      (node (ref "D_ADR_4") (pin "1") (pinfunction "K_1") (pintype "passive"))
      (node (ref "D_BB_4") (pin "1") (pinfunction "K_1") (pintype "passive"))
      (node (ref "U100") (pin "29") (pinfunction "PA8_29") (pintype "bidirectional"))
    )
    (net (code "45") (name "/DATA_BUS_A5") (class "Default")
      (node (ref "D_ADR_5") (pin "1") (pinfunction "K_1") (pintype "passive"))
      (node (ref "D_BB_5") (pin "1") (pinfunction "K_1") (pintype "passive"))
      (node (ref "U100") (pin "12") (pinfunction "PA2_12") (pintype "bidirectional"))
    )
    (net (code "46") (name "/DATA_BUS_A6") (class "Default")
      (node (ref "D_ADR_6") (pin "1") (pinfunction "K_1") (pintype "passive"))
      (node (ref "D_BB_6") (pin "1") (pinfunction "K_1") (pintype "passive"))
      (node (ref "U100") (pin "13") (pinfunction "PA3_13") (pintype "bidirectional"))
    )
    (net (code "47") (name "/GND") (class "Default")
      (node (ref "C100") (pin "1") (pinfunction "1_1") (pintype "passive"))
      (node (ref "C101") (pin "1") (pinfunction "1_1") (pintype "passive"))
      (node (ref "C102") (pin "1") (pinfunction "1_1") (pintype "passive"))
      (node (ref "C103") (pin "1") (pinfunction "1_1") (pintype "passive"))
      (node (ref "C104") (pin "1") (pinfunction "1_1") (pintype "passive"))
      (node (ref "C106") (pin "1") (pinfunction "1_1") (pintype "passive"))
      (node (ref "C107") (pin "1") (pinfunction "1_1") (pintype "passive"))
      (node (ref "C2") (pin "1") (pinfunction "1_1") (pintype "passive"))
      (node (ref "CAP1") (pin "2") (pinfunction "2_2") (pintype "passive"))
      (node (ref "CAPSRC") (pin "2") (pinfunction "2_2") (pintype "passive"))
      (node (ref "CC0A") (pin "2") (pinfunction "2_2") (pintype "passive"))
      (node (ref "CC0B") (pin "1") (pinfunction "1_1") (pintype "passive"))
      (node (ref "CR1") (pin "2") (pinfunction "2_2") (pintype "passive"))
      (node (ref "CR2") (pin "2") (pinfunction "2_2") (pintype "passive"))
      (node (ref "CR3") (pin "2") (pinfunction "2_2") (pintype "passive"))
      (node (ref "CSNS0") (pin "1") (pinfunction "1_1") (pintype "passive"))
      (node (ref "CSNS2") (pin "2") (pinfunction "2_2") (pintype "passive"))
      (node (ref "DS_VCC") (pin "2") (pinfunction "A_2") (pintype "passive"))
      (node (ref "J100") (pin "0") (pinfunction "SHLD_0") (pintype "passive"))
      (node (ref "J100") (pin "A12_B1") (pinfunction "GND_A12_B1") (pintype "passive"))
      (node (ref "J100") (pin "A1_B12") (pinfunction "GND_A1_B12") (pintype "passive"))
      (node (ref "NT_0") (pin "2") (pinfunction "2_2") (pintype "passive"))
      (node (ref "NT_1") (pin "2") (pinfunction "2_2") (pintype "passive"))
      (node (ref "Q12") (pin "2") (pinfunction "S_2") (pintype "passive"))
      (node (ref "Q13") (pin "2") (pinfunction "S_2") (pintype "passive"))
      (node (ref "Q14") (pin "2") (pinfunction "S_2") (pintype "passive"))
      (node (ref "Q18") (pin "2") (pinfunction "S_2") (pintype "passive"))
      (node (ref "QBEN") (pin "2") (pinfunction "S_2") (pintype "passive"))
      (node (ref "QBENR") (pin "2") (pinfunction "2_2") (pintype "passive"))
      (node (ref "R102") (pin "1") (pinfunction "1_1") (pintype "passive"))
      (node (ref "R108") (pin "1") (pinfunction "1_1") (pintype "passive"))
      (node (ref "R109") (pin "1") (pinfunction "1_1") (pintype "passive"))
      (node (ref "R110") (pin "2") (pinfunction "2_2") (pintype "passive"))
      (node (ref "RBUS_3") (pin "1") (pinfunction "1_1") (pintype "passive"))
      (node (ref "RSNS") (pin "1") (pinfunction "1_1") (pintype "passive"))
      (node (ref "RSNSP") (pin "1") (pinfunction "1_1") (pintype "passive"))
      (node (ref "U1") (pin "3") (pinfunction "VSS_3") (pintype "passive"))
      (node (ref "U100") (pin "23") (pinfunction "VSS_1_23") (pintype "power_in"))
      (node (ref "U100") (pin "35") (pinfunction "VSS_2_35") (pintype "power_in"))
      (node (ref "U100") (pin "44") (pinfunction "BOOT0_44") (pintype "input"))
      (node (ref "U100") (pin "47") (pinfunction "VSS_3_47") (pintype "power_in"))
      (node (ref "U101") (pin "1") (pinfunction "VSS_1") (pintype "power_in"))
      (node (ref "U2") (pin "12") (pinfunction "VSS_12") (pintype "power_in"))
    )
    (net (code "48") (name "/GQBD") (class "Default")
      (node (ref "DBD_2") (pin "2") (pinfunction "A_2") (pintype "passive"))
      (node (ref "GQBDR") (pin "2") (pinfunction "2_2") (pintype "passive"))
      (node (ref "QBD_1A") (pin "1") (pinfunction "G_1") (pintype "passive"))
      (node (ref "QBD_1B") (pin "1") (pinfunction "G_1") (pintype "passive"))
      (node (ref "QBD_2A") (pin "1") (pinfunction "G_1") (pintype "passive"))
      (node (ref "QBD_2B") (pin "1") (pinfunction "G_1") (pintype "passive"))
      (node (ref "QBD_3A") (pin "1") (pinfunction "G_1") (pintype "passive"))
      (node (ref "QBD_3B") (pin "1") (pinfunction "G_1") (pintype "passive"))
      (node (ref "QBD_4A") (pin "1") (pinfunction "G_1") (pintype "passive"))
      (node (ref "QBD_4B") (pin "1") (pinfunction "G_1") (pintype "passive"))
      (node (ref "QBD_5A") (pin "1") (pinfunction "G_1") (pintype "passive"))
      (node (ref "QBD_5B") (pin "1") (pinfunction "G_1") (pintype "passive"))
      (node (ref "RBEN") (pin "2") (pinfunction "2_2") (pintype "passive"))
    )
    (net (code "49") (name "/GQS") (class "Default")
      (node (ref "DBD_1") (pin "1") (pinfunction "K_1") (pintype "passive"))
      (node (ref "GQBDR") (pin "1") (pinfunction "1_1") (pintype "passive"))
      (node (ref "QBD_1A") (pin "3") (pinfunction "S_3") (pintype "passive"))
      (node (ref "QBD_1B") (pin "3") (pinfunction "S_3") (pintype "passive"))
      (node (ref "QBD_2A") (pin "3") (pinfunction "S_3") (pintype "passive"))
      (node (ref "QBD_2B") (pin "3") (pinfunction "S_3") (pintype "passive"))
      (node (ref "QBD_3A") (pin "3") (pinfunction "S_3") (pintype "passive"))
      (node (ref "QBD_3B") (pin "3") (pinfunction "S_3") (pintype "passive"))
      (node (ref "QBD_4A") (pin "3") (pinfunction "S_3") (pintype "passive"))
      (node (ref "QBD_4B") (pin "3") (pinfunction "S_3") (pintype "passive"))
      (node (ref "QBD_5A") (pin "3") (pinfunction "S_3") (pintype "passive"))
      (node (ref "QBD_5B") (pin "3") (pinfunction "S_3") (pintype "passive"))
    )
    (net (code "50") (name "/HOTPLUG_OUT") (class "Default")
      (node (ref "D_3V3_O") (pin "1") (pinfunction "K_1") (pintype "passive"))
    )
    (net (code "51") (name "/I2C_A0") (class "Default")
      (node (ref "D_ADR_0") (pin "2") (pinfunction "A_2") (pintype "passive"))
    )
    (net (code "52") (name "/I2C_A1") (class "Default")
      (node (ref "D_ADR_1") (pin "2") (pinfunction "A_2") (pintype "passive"))
    )
    (net (code "53") (name "/I2C_A2") (class "Default")
      (node (ref "D_ADR_2") (pin "2") (pinfunction "A_2") (pintype "passive"))
    )
    (net (code "54") (name "/I2C_A3") (class "Default")
      (node (ref "D_ADR_3") (pin "2") (pinfunction "A_2") (pintype "passive"))
    )
    (net (code "55") (name "/I2C_A4") (class "Default")
      (node (ref "D_ADR_4") (pin "2") (pinfunction "A_2") (pintype "passive"))
    )
    (net (code "56") (name "/I2C_A5") (class "Default")
      (node (ref "D_ADR_5") (pin "2") (pinfunction "A_2") (pintype "passive"))
    )
    (net (code "57") (name "/I2C_A6") (class "Default")
      (node (ref "D_ADR_6") (pin "2") (pinfunction "A_2") (pintype "passive"))
    )
    (net (code "58") (name "/I2C_ASNS") (class "Default")
      (node (ref "D_ADR_VCC") (pin "1") (pinfunction "K_1") (pintype "passive"))
    )
    (net (code "59") (name "/LED_4") (class "Default")
      (node (ref "RLED_4") (pin "2") (pinfunction "2_2") (pintype "passive"))
      (node (ref "U100") (pin "4") (pinfunction "PC15-OSC32_OUT_4") (pintype "bidirectional"))
    )
    (net (code "60") (name "/NRST") (class "Default")
      (node (ref "C106") (pin "2") (pinfunction "2_2") (pintype "passive"))
      (node (ref "U100") (pin "7") (pinfunction "NRST_7") (pintype "bidirectional"))
    )
    (net (code "61") (name "/PACK+") (class "Default")
      (node (ref "QBD_1A") (pin "2") (pinfunction "D_2") (pintype "passive"))
      (node (ref "QBD_2A") (pin "2") (pinfunction "D_2") (pintype "passive"))
      (node (ref "QBD_3A") (pin "2") (pinfunction "D_2") (pintype "passive"))
      (node (ref "QBD_4A") (pin "2") (pinfunction "D_2") (pintype "passive"))
      (node (ref "QBD_5A") (pin "2") (pinfunction "D_2") (pintype "passive"))
      (node (ref "RBUS_1") (pin "2") (pinfunction "2_2") (pintype "passive"))
    )
    (net (code "62") (name "/PACK-") (class "Default")
      (node (ref "RSNS") (pin "2") (pinfunction "2_2") (pintype "passive"))
      (node (ref "RSNSN") (pin "1") (pinfunction "1_1") (pintype "passive"))
    )
    (net (code "63") (name "/REGSRC") (class "Default")
      (node (ref "CAPSRC") (pin "1") (pinfunction "1_1") (pintype "passive"))
      (node (ref "RSHUNT3") (pin "1") (pinfunction "1_1") (pintype "passive"))
      (node (ref "U1") (pin "9") (pinfunction "REGSRC_9") (pintype "passive"))
    )
    (net (code "64") (name "/SIN") (class "Default")
      (node (ref "U100") (pin "17") (pinfunction "PA7_17") (pintype "bidirectional"))
    )
    (net (code "65") (name "/SRN") (class "Default")
      (node (ref "CSNS0") (pin "2") (pinfunction "2_2") (pintype "passive"))
      (node (ref "CSNS1") (pin "1") (pinfunction "1_1") (pintype "passive"))
      (node (ref "RSNSN") (pin "2") (pinfunction "2_2") (pintype "passive"))
      (node (ref "U1") (pin "43") (pinfunction "SRN_43") (pintype "passive"))
    )
    (net (code "66") (name "/SRP") (class "Default")
      (node (ref "CSNS1") (pin "2") (pinfunction "2_2") (pintype "passive"))
      (node (ref "CSNS2") (pin "1") (pinfunction "1_1") (pintype "passive"))
      (node (ref "RSNSP") (pin "2") (pinfunction "2_2") (pintype "passive"))
      (node (ref "U1") (pin "42") (pinfunction "SRP_42") (pintype "passive"))
    )
    (net (code "67") (name "/STAYUP") (class "Default")
      (node (ref "D11") (pin "2") (pinfunction "A_2") (pintype "passive"))
      (node (ref "U100") (pin "19") (pinfunction "PB1_19") (pintype "bidirectional"))
    )
    (net (code "68") (name "/SWCLK") (class "Default")
      (node (ref "U100") (pin "37") (pinfunction "PA14_37") (pintype "bidirectional"))
    )
    (net (code "69") (name "/SWDIO") (class "Default")
      (node (ref "U100") (pin "34") (pinfunction "PA13_34") (pintype "bidirectional"))
    )
    (net (code "70") (name "/TS2") (class "Default")
      (node (ref "U1") (pin "13") (pinfunction "TS2_13") (pintype "passive"))
    )
    (net (code "71") (name "/TS3") (class "Default")
      (node (ref "U1") (pin "18") (pinfunction "TS3_18") (pintype "passive"))
    )
    (net (code "72") (name "/TS_0") (class "Default")
      (node (ref "CTS_0A") (pin "2") (pinfunction "2_2") (pintype "passive"))
      (node (ref "CTS_0B") (pin "2") (pinfunction "2_2") (pintype "passive"))
      (node (ref "RT_0A") (pin "1") (pinfunction "1_1") (pintype "passive"))
      (node (ref "RT_0B") (pin "1") (pinfunction "1_1") (pintype "passive"))
      (node (ref "U2") (pin "9") (pinfunction "Y0_9") (pintype "passive"))
    )
    (net (code "73") (name "/TS_1") (class "Default")
      (node (ref "CTS_1A") (pin "2") (pinfunction "2_2") (pintype "passive"))
      (node (ref "CTS_1B") (pin "2") (pinfunction "2_2") (pintype "passive"))
      (node (ref "RT_1A") (pin "1") (pinfunction "1_1") (pintype "passive"))
      (node (ref "RT_1B") (pin "1") (pinfunction "1_1") (pintype "passive"))
      (node (ref "U2") (pin "8") (pinfunction "Y1_8") (pintype "passive"))
    )
    (net (code "74") (name "/TS_2") (class "Default")
      (node (ref "CTS_2A") (pin "2") (pinfunction "2_2") (pintype "passive"))
      (node (ref "CTS_2B") (pin "2") (pinfunction "2_2") (pintype "passive"))
      (node (ref "RT_2A") (pin "1") (pinfunction "1_1") (pintype "passive"))
      (node (ref "RT_2B") (pin "1") (pinfunction "1_1") (pintype "passive"))
      (node (ref "U2") (pin "7") (pinfunction "Y2_7") (pintype "passive"))
    )
    (net (code "75") (name "/TS_3") (class "Default")
      (node (ref "CTS_3A") (pin "2") (pinfunction "2_2") (pintype "passive"))
      (node (ref "CTS_3B") (pin "2") (pinfunction "2_2") (pintype "passive"))
      (node (ref "RT_3A") (pin "1") (pinfunction "1_1") (pintype "passive"))
      (node (ref "RT_3B") (pin "1") (pinfunction "1_1") (pintype "passive"))
      (node (ref "U2") (pin "6") (pinfunction "Y3_6") (pintype "passive"))
    )
    (net (code "76") (name "/TS_4") (class "Default")
      (node (ref "CTS_4A") (pin "2") (pinfunction "2_2") (pintype "passive"))
      (node (ref "CTS_4B") (pin "2") (pinfunction "2_2") (pintype "passive"))
      (node (ref "RT_4A") (pin "1") (pinfunction "1_1") (pintype "passive"))
      (node (ref "RT_4B") (pin "1") (pinfunction "1_1") (pintype "passive"))
      (node (ref "U2") (pin "5") (pinfunction "Y4_5") (pintype "passive"))
    )
    (net (code "77") (name "/TS_5") (class "Default")
      (node (ref "CTS_5A") (pin "2") (pinfunction "2_2") (pintype "passive"))
      (node (ref "CTS_5B") (pin "2") (pinfunction "2_2") (pintype "passive"))
      (node (ref "RT_5A") (pin "1") (pinfunction "1_1") (pintype "passive"))
      (node (ref "RT_5B") (pin "1") (pinfunction "1_1") (pintype "passive"))
      (node (ref "U2") (pin "4") (pinfunction "Y5_4") (pintype "passive"))
    )
    (net (code "78") (name "/TS_6") (class "Default")
      (node (ref "CTS_6A") (pin "2") (pinfunction "2_2") (pintype "passive"))
      (node (ref "CTS_6B") (pin "2") (pinfunction "2_2") (pintype "passive"))
      (node (ref "RT_6A") (pin "1") (pinfunction "1_1") (pintype "passive"))
      (node (ref "RT_6B") (pin "1") (pinfunction "1_1") (pintype "passive"))
      (node (ref "U2") (pin "3") (pinfunction "Y6_3") (pintype "passive"))
    )
    (net (code "79") (name "/TS_7") (class "Default")
      (node (ref "CTS_7A") (pin "2") (pinfunction "2_2") (pintype "passive"))
      (node (ref "CTS_7B") (pin "2") (pinfunction "2_2") (pintype "passive"))
      (node (ref "RT_7A") (pin "1") (pinfunction "1_1") (pintype "passive"))
      (node (ref "RT_7B") (pin "1") (pinfunction "1_1") (pintype "passive"))
      (node (ref "U2") (pin "2") (pinfunction "Y7_2") (pintype "passive"))
    )
    (net (code "80") (name "/TS_8") (class "Default")
      (node (ref "CTS_8A") (pin "2") (pinfunction "2_2") (pintype "passive"))
      (node (ref "CTS_8B") (pin "2") (pinfunction "2_2") (pintype "passive"))
      (node (ref "RT_8A") (pin "1") (pinfunction "1_1") (pintype "passive"))
      (node (ref "RT_8B") (pin "1") (pinfunction "1_1") (pintype "passive"))
      (node (ref "U2") (pin "23") (pinfunction "Y8_23") (pintype "passive"))
    )
    (net (code "81") (name "/TS_9") (class "Default")
      (node (ref "CTS_9A") (pin "2") (pinfunction "2_2") (pintype "passive"))
      (node (ref "CTS_9B") (pin "2") (pinfunction "2_2") (pintype "passive"))
      (node (ref "RT_9A") (pin "1") (pinfunction "1_1") (pintype "passive"))
      (node (ref "RT_9B") (pin "1") (pinfunction "1_1") (pintype "passive"))
      (node (ref "U2") (pin "22") (pinfunction "Y9_22") (pintype "passive"))
    )
    (net (code "82") (name "/TS_10") (class "Default")
      (node (ref "CTS_10A") (pin "2") (pinfunction "2_2") (pintype "passive"))
      (node (ref "CTS_10B") (pin "2") (pinfunction "2_2") (pintype "passive"))
      (node (ref "RT_10A") (pin "1") (pinfunction "1_1") (pintype "passive"))
      (node (ref "RT_10B") (pin "1") (pinfunction "1_1") (pintype "passive"))
      (node (ref "U2") (pin "21") (pinfunction "Y10_21") (pintype "passive"))
    )
    (net (code "83") (name "/TS_11") (class "Default")
      (node (ref "CTS_11A") (pin "2") (pinfunction "2_2") (pintype "passive"))
      (node (ref "CTS_11B") (pin "2") (pinfunction "2_2") (pintype "passive"))
      (node (ref "RT_11A") (pin "1") (pinfunction "1_1") (pintype "passive"))
      (node (ref "RT_11B") (pin "1") (pinfunction "1_1") (pintype "passive"))
      (node (ref "U2") (pin "20") (pinfunction "Y11_20") (pintype "passive"))
    )
    (net (code "84") (name "/TS_12") (class "Default")
      (node (ref "CTS_12A") (pin "2") (pinfunction "2_2") (pintype "passive"))
      (node (ref "CTS_12B") (pin "2") (pinfunction "2_2") (pintype "passive"))
      (node (ref "RT_12A") (pin "1") (pinfunction "1_1") (pintype "passive"))
      (node (ref "RT_12B") (pin "1") (pinfunction "1_1") (pintype "passive"))
      (node (ref "U2") (pin "19") (pinfunction "Y12_19") (pintype "passive"))
    )
    (net (code "85") (name "/TS_13") (class "Default")
      (node (ref "CTS_13A") (pin "2") (pinfunction "2_2") (pintype "passive"))
      (node (ref "CTS_13B") (pin "2") (pinfunction "2_2") (pintype "passive"))
      (node (ref "RT_13A") (pin "1") (pinfunction "1_1") (pintype "passive"))
      (node (ref "RT_13B") (pin "1") (pinfunction "1_1") (pintype "passive"))
      (node (ref "U2") (pin "18") (pinfunction "Y13_18") (pintype "passive"))
    )
    (net (code "86") (name "/TS_14") (class "Default")
      (node (ref "CTS_14A") (pin "2") (pinfunction "2_2") (pintype "passive"))
      (node (ref "CTS_14B") (pin "2") (pinfunction "2_2") (pintype "passive"))
      (node (ref "RT_14A") (pin "1") (pinfunction "1_1") (pintype "passive"))
      (node (ref "RT_14B") (pin "1") (pinfunction "1_1") (pintype "passive"))
      (node (ref "U2") (pin "17") (pinfunction "Y14_17") (pintype "passive"))
    )
    (net (code "87") (name "/TS_15") (class "Default")
      (node (ref "CTS_15") (pin "2") (pinfunction "2_2") (pintype "passive"))
      (node (ref "RTS2") (pin "2") (pinfunction "2_2") (pintype "passive"))
      (node (ref "RT_15B") (pin "1") (pinfunction "1_1") (pintype "passive"))
      (node (ref "U2") (pin "16") (pinfunction "Y15_16") (pintype "passive"))
    )
    (net (code "88") (name "/TS_A_GND") (class "Default")
      (node (ref "CTS_0A") (pin "1") (pinfunction "1_1") (pintype "passive"))
      (node (ref "CTS_10A") (pin "1") (pinfunction "1_1") (pintype "passive"))
      (node (ref "CTS_11A") (pin "1") (pinfunction "1_1") (pintype "passive"))
      (node (ref "CTS_12A") (pin "1") (pinfunction "1_1") (pintype "passive"))
      (node (ref "CTS_13A") (pin "1") (pinfunction "1_1") (pintype "passive"))
      (node (ref "CTS_14A") (pin "1") (pinfunction "1_1") (pintype "passive"))
      (node (ref "CTS_1A") (pin "1") (pinfunction "1_1") (pintype "passive"))
      (node (ref "CTS_2A") (pin "1") (pinfunction "1_1") (pintype "passive"))
      (node (ref "CTS_3A") (pin "1") (pinfunction "1_1") (pintype "passive"))
      (node (ref "CTS_4A") (pin "1") (pinfunction "1_1") (pintype "passive"))
      (node (ref "CTS_5A") (pin "1") (pinfunction "1_1") (pintype "passive"))
      (node (ref "CTS_6A") (pin "1") (pinfunction "1_1") (pintype "passive"))
      (node (ref "CTS_7A") (pin "1") (pinfunction "1_1") (pintype "passive"))
      (node (ref "CTS_8A") (pin "1") (pinfunction "1_1") (pintype "passive"))
      (node (ref "CTS_9A") (pin "1") (pinfunction "1_1") (pintype "passive"))
      (node (ref "TSQ1a") (pin "3") (pinfunction "D_3") (pintype "passive"))
    )
    (net (code "89") (name "/TS_B_GND") (class "Default")
      (node (ref "CTS_0B") (pin "1") (pinfunction "1_1") (pintype "passive"))
      (node (ref "CTS_10B") (pin "1") (pinfunction "1_1") (pintype "passive"))
      (node (ref "CTS_11B") (pin "1") (pinfunction "1_1") (pintype "passive"))
      (node (ref "CTS_12B") (pin "1") (pinfunction "1_1") (pintype "passive"))
      (node (ref "CTS_13B") (pin "1") (pinfunction "1_1") (pintype "passive"))
      (node (ref "CTS_14B") (pin "1") (pinfunction "1_1") (pintype "passive"))
      (node (ref "CTS_1B") (pin "1") (pinfunction "1_1") (pintype "passive"))
      (node (ref "CTS_2B") (pin "1") (pinfunction "1_1") (pintype "passive"))
      (node (ref "CTS_3B") (pin "1") (pinfunction "1_1") (pintype "passive"))
      (node (ref "CTS_4B") (pin "1") (pinfunction "1_1") (pintype "passive"))
      (node (ref "CTS_5B") (pin "1") (pinfunction "1_1") (pintype "passive"))
      (node (ref "CTS_6B") (pin "1") (pinfunction "1_1") (pintype "passive"))
      (node (ref "CTS_7B") (pin "1") (pinfunction "1_1") (pintype "passive"))
      (node (ref "CTS_8B") (pin "1") (pinfunction "1_1") (pintype "passive"))
      (node (ref "CTS_9B") (pin "1") (pinfunction "1_1") (pintype "passive"))
      (node (ref "TSQ1b") (pin "3") (pinfunction "D_3") (pintype "passive"))
    )
    (net (code "90") (name "/TS_EN_A") (class "Default")
      (node (ref "D1") (pin "2") (pinfunction "A_2") (pintype "passive"))
      (node (ref "TSQ1a") (pin "1") (pinfunction "G_1") (pintype "passive"))
      (node (ref "U100") (pin "45") (pinfunction "PB8_45") (pintype "bidirectional"))
    )
    (net (code "91") (name "/TS_EN_B") (class "Default")
      (node (ref "D2") (pin "2") (pinfunction "A_2") (pintype "passive"))
      (node (ref "TSQ1b") (pin "1") (pinfunction "G_1") (pintype "passive"))
      (node (ref "U100") (pin "46") (pinfunction "PB9_46") (pintype "bidirectional"))
    )
    (net (code "92") (name "/TS_EN_MUX") (class "Default")
      (node (ref "D1") (pin "1") (pinfunction "K_1") (pintype "passive"))
      (node (ref "D2") (pin "1") (pinfunction "K_1") (pintype "passive"))
      (node (ref "U2") (pin "15") (pinfunction "E_15") (pintype "passive"))
    )
    (net (code "93") (name "/TS_MULTIPLEXED") (class "Default")
      (node (ref "R2") (pin "2") (pinfunction "2_2") (pintype "passive"))
      (node (ref "U2") (pin "1") (pinfunction "Z_1") (pintype "passive"))
    )
    (net (code "94") (name "/TS_MUX_FILTERED") (class "Default")
      (node (ref "C2") (pin "2") (pinfunction "2_2") (pintype "passive"))
      (node (ref "R2") (pin "1") (pinfunction "1_1") (pintype "passive"))
      (node (ref "U100") (pin "15") (pinfunction "PA5_15") (pintype "bidirectional"))
    )
    (net (code "95") (name "/USB_DM") (class "Default")
      (node (ref "J100") (pin "A7") (pinfunction "D1_N_A7") (pintype "passive"))
      (node (ref "J100") (pin "B7") (pinfunction "D2_N_B7") (pintype "passive"))
      (node (ref "R100") (pin "1") (pinfunction "1_1") (pintype "passive"))
    )
    (net (code "96") (name "/USB_DM_R") (class "Default")
      (node (ref "R100") (pin "2") (pinfunction "2_2") (pintype "passive"))
      (node (ref "U100") (pin "32") (pinfunction "PA11_32") (pintype "bidirectional"))
    )
    (net (code "97") (name "/USB_DP") (class "Default")
      (node (ref "J100") (pin "A6") (pinfunction "D1_P_A6") (pintype "passive"))
      (node (ref "J100") (pin "B6") (pinfunction "D2_P_B6") (pintype "passive"))
      (node (ref "R101") (pin "1") (pinfunction "1_1") (pintype "passive"))
    )
    (net (code "98") (name "/USB_DP_R") (class "Default")
      (node (ref "R101") (pin "2") (pinfunction "2_2") (pintype "passive"))
      (node (ref "R106") (pin "1") (pinfunction "1_1") (pintype "passive"))
      (node (ref "U100") (pin "33") (pinfunction "PA12_33") (pintype "bidirectional"))
    )
    (net (code "99") (name "/VBUS_S") (class "Default")
      (node (ref "RBUS_2") (pin "1") (pinfunction "1_1") (pintype "passive"))
      (node (ref "RBUS_3") (pin "2") (pinfunction "2_2") (pintype "passive"))
      (node (ref "U100") (pin "18") (pinfunction "PB0_18") (pintype "bidirectional"))
    )
    (net (code "100") (name "/VC5x") (class "Default")
      (node (ref "CAP2") (pin "2") (pinfunction "2_2") (pintype "passive"))
      (node (ref "CC5A") (pin "2") (pinfunction "2_2") (pintype "passive"))
      (node (ref "CC5B") (pin "1") (pinfunction "1_1") (pintype "passive"))
      (node (ref "DC5") (pin "1") (pinfunction "K_1") (pintype "passive"))
      (node (ref "RSHUNT") (pin "1") (pinfunction "1_1") (pintype "passive"))
      (node (ref "U1") (pin "10") (pinfunction "VC5x_10") (pintype "passive"))
    )
    (net (code "101") (name "/VC10x") (class "Default")
      (node (ref "CAP3") (pin "2") (pinfunction "2_2") (pintype "passive"))
      (node (ref "CC10A") (pin "2") (pinfunction "2_2") (pintype "passive"))
      (node (ref "CC10B") (pin "1") (pinfunction "1_1") (pintype "passive"))
      (node (ref "DC10") (pin "1") (pinfunction "K_1") (pintype "passive"))
      (node (ref "U1") (pin "15") (pinfunction "VC10x_15") (pintype "passive"))
    )
    (net (code "102") (name "/VCC_3V3") (class "Default")
      (node (ref "C102") (pin "2") (pinfunction "2_2") (pintype "passive"))
      (node (ref "C103") (pin "2") (pinfunction "2_2") (pintype "passive"))
      (node (ref "C104") (pin "2") (pinfunction "2_2") (pintype "passive"))
      (node (ref "D_3V3_O") (pin "2") (pinfunction "A_2") (pintype "passive"))
      (node (ref "L100") (pin "2") (pinfunction "2_2") (pintype "passive"))
      (node (ref "Q_3V3") (pin "3") (pinfunction "D_3") (pintype "passive"))
      (node (ref "R106") (pin "2") (pinfunction "2_2") (pintype "passive"))
      (node (ref "SW1") (pin "2") (pinfunction "2_2") (pintype "passive"))
      (node (ref "U100") (pin "1") (pinfunction "VBAT_1") (pintype "power_in"))
      (node (ref "U100") (pin "24") (pinfunction "VDD_1_24") (pintype "power_in"))
      (node (ref "U100") (pin "36") (pinfunction "VDD_2_36") (pintype "power_in"))
      (node (ref "U100") (pin "48") (pinfunction "VDD_3_48") (pintype "power_in"))
      (node (ref "U101") (pin "2") (pinfunction "Vout_2") (pintype "output"))
    )
    (net (code "103") (name "/VCC_3V3_2") (class "Default")
      (node (ref "CR1") (pin "1") (pinfunction "1_1") (pintype "passive"))
      (node (ref "CR2") (pin "1") (pinfunction "1_1") (pintype "passive"))
      (node (ref "CR3") (pin "1") (pinfunction "1_1") (pintype "passive"))
      (node (ref "NT_2") (pin "2") (pinfunction "2_2") (pintype "passive"))
      (node (ref "U1") (pin "8") (pinfunction "REGOUT_8") (pintype "passive"))
    )
    (net (code "104") (name "/VCC_3V3_SW") (class "Default")
      (node (ref "3V3R1") (pin "1") (pinfunction "1_1") (pintype "passive"))
      (node (ref "LED_1") (pin "2") (pinfunction "A_2") (pintype "passive"))
      (node (ref "LED_2") (pin "2") (pinfunction "A_2") (pintype "passive"))
      (node (ref "LED_3") (pin "2") (pinfunction "A_2") (pintype "passive"))
      (node (ref "LED_4") (pin "2") (pinfunction "A_2") (pintype "passive"))
      (node (ref "NT_2") (pin "1") (pinfunction "1_1") (pintype "passive"))
      (node (ref "Q_3V3") (pin "2") (pinfunction "S_2") (pintype "passive"))
      (node (ref "RSCL") (pin "1") (pinfunction "1_1") (pintype "passive"))
      (node (ref "RSDA") (pin "1") (pinfunction "1_1") (pintype "passive"))
      (node (ref "RT_0A") (pin "2") (pinfunction "2_2") (pintype "passive"))
      (node (ref "RT_0B") (pin "2") (pinfunction "2_2") (pintype "passive"))
      (node (ref "RT_10A") (pin "2") (pinfunction "2_2") (pintype "passive"))
      (node (ref "RT_10B") (pin "2") (pinfunction "2_2") (pintype "passive"))
      (node (ref "RT_11A") (pin "2") (pinfunction "2_2") (pintype "passive"))
      (node (ref "RT_11B") (pin "2") (pinfunction "2_2") (pintype "passive"))
      (node (ref "RT_12A") (pin "2") (pinfunction "2_2") (pintype "passive"))
      (node (ref "RT_12B") (pin "2") (pinfunction "2_2") (pintype "passive"))
      (node (ref "RT_13A") (pin "2") (pinfunction "2_2") (pintype "passive"))
      (node (ref "RT_13B") (pin "2") (pinfunction "2_2") (pintype "passive"))
      (node (ref "RT_14A") (pin "2") (pinfunction "2_2") (pintype "passive"))
      (node (ref "RT_14B") (pin "2") (pinfunction "2_2") (pintype "passive"))
      (node (ref "RT_15B") (pin "2") (pinfunction "2_2") (pintype "passive"))
      (node (ref "RT_1A") (pin "2") (pinfunction "2_2") (pintype "passive"))
      (node (ref "RT_1B") (pin "2") (pinfunction "2_2") (pintype "passive"))
      (node (ref "RT_2A") (pin "2") (pinfunction "2_2") (pintype "passive"))
      (node (ref "RT_2B") (pin "2") (pinfunction "2_2") (pintype "passive"))
      (node (ref "RT_3A") (pin "2") (pinfunction "2_2") (pintype "passive"))
      (node (ref "RT_3B") (pin "2") (pinfunction "2_2") (pintype "passive"))
      (node (ref "RT_4A") (pin "2") (pinfunction "2_2") (pintype "passive"))
      (node (ref "RT_4B") (pin "2") (pinfunction "2_2") (pintype "passive"))
      (node (ref "RT_5A") (pin "2") (pinfunction "2_2") (pintype "passive"))
      (node (ref "RT_5B") (pin "2") (pinfunction "2_2") (pintype "passive"))
      (node (ref "RT_6A") (pin "2") (pinfunction "2_2") (pintype "passive"))
      (node (ref "RT_6B") (pin "2") (pinfunction "2_2") (pintype "passive"))
      (node (ref "RT_7A") (pin "2") (pinfunction "2_2") (pintype "passive"))
      (node (ref "RT_7B") (pin "2") (pinfunction "2_2") (pintype "passive"))
      (node (ref "RT_8A") (pin "2") (pinfunction "2_2") (pintype "passive"))
      (node (ref "RT_8B") (pin "2") (pinfunction "2_2") (pintype "passive"))
      (node (ref "RT_9A") (pin "2") (pinfunction "2_2") (pintype "passive"))
      (node (ref "RT_9B") (pin "2") (pinfunction "2_2") (pintype "passive"))
      (node (ref "U2") (pin "24") (pinfunction "VCC_24") (pintype "power_in"))
    )
    (net (code "105") (name "/VCC_5V1") (class "Default")
      (node (ref "C107") (pin "2") (pinfunction "2_2") (pintype "passive"))
      (node (ref "D5V1_SB") (pin "1") (pinfunction "K_1") (pintype "passive"))
      (node (ref "DS_VCC") (pin "1") (pinfunction "K_1") (pintype "passive"))
      (node (ref "J100") (pin "A4_B9") (pinfunction "VBUS_A4_B9") (pintype "power_in"))
      (node (ref "J100") (pin "A9_B4") (pinfunction "VBUS_A9_B4") (pintype "power_in"))
      (node (ref "Q19") (pin "2") (pinfunction "S_2") (pintype "passive"))
      (node (ref "U101") (pin "3") (pinfunction "VIN_3") (pintype "input"))
    )
    (net (code "106") (name "/VCC_STBY") (class "Default")
      (node (ref "D5V1_SB") (pin "2") (pinfunction "A_2") (pintype "passive"))
    )
    (net (code "107") (name "/VCMOS") (class "Default")
      (node (ref "Q10") (pin "3") (pinfunction "D_3") (pintype "passive"))
      (node (ref "R10") (pin "2") (pinfunction "2_2") (pintype "passive"))
      (node (ref "R11") (pin "1") (pinfunction "1_1") (pintype "passive"))
      (node (ref "R_CMOS") (pin "2") (pinfunction "2_2") (pintype "passive"))
    )
    (net (code "108") (name "/VDDA") (class "Default")
      (node (ref "C105") (pin "2") (pinfunction "2_2") (pintype "passive"))
      (node (ref "L100") (pin "1") (pinfunction "1_1") (pintype "passive"))
      (node (ref "U100") (pin "9") (pinfunction "VDDA_9") (pintype "power_in"))
    )
    (net (code "109") (name "/WAKEUP") (class "Default")
      (node (ref "Q11") (pin "1") (pinfunction "G_1") (pintype "passive"))
      (node (ref "Q13") (pin "1") (pinfunction "G_1") (pintype "passive"))
      (node (ref "U100") (pin "10") (pinfunction "PA0-WKUP_10") (pintype "bidirectional"))
    )
    (net (code "110") (name "/^PB2_BOOT1") (class "Default")
      (node (ref "R110") (pin "1") (pinfunction "1_1") (pintype "passive"))
      (node (ref "SW1") (pin "1") (pinfunction "1_1") (pintype "passive"))
      (node (ref "U100") (pin "20") (pinfunction "PB2_20") (pintype "bidirectional"))
    )
    (net (code "111") (name "/^PB3{slash}PPS") (class "Default")
      (node (ref "RLED_3") (pin "2") (pinfunction "2_2") (pintype "passive"))
      (node (ref "U100") (pin "39") (pinfunction "PB3_39") (pintype "bidirectional"))
    )
    (net (code "112") (name "/^PB14_MISO2") (class "Default")
      (node (ref "RLED_1") (pin "2") (pinfunction "2_2") (pintype "passive"))
      (node (ref "U100") (pin "27") (pinfunction "PB14_27") (pintype "bidirectional"))
    )
    (net (code "113") (name "/^PB15_MOSI2") (class "Default")
      (node (ref "RLED_2") (pin "2") (pinfunction "2_2") (pintype "passive"))
      (node (ref "U100") (pin "28") (pinfunction "PB15_28") (pintype "bidirectional"))
    )
    (net (code "114") (name "Net-(D10-A)") (class "Default")
      (node (ref "D10") (pin "2") (pinfunction "A_2") (pintype "passive"))
      (node (ref "Q10") (pin "1") (pinfunction "G_1") (pintype "passive"))
      (node (ref "Q12") (pin "1") (pinfunction "G_1") (pintype "passive"))
      (node (ref "Q14") (pin "3") (pinfunction "D_3") (pintype "passive"))
      (node (ref "Q15") (pin "2") (pinfunction "S_2") (pintype "passive"))
    )
    (net (code "115") (name "Net-(D10-K)") (class "Default")
      (node (ref "D10") (pin "1") (pinfunction "K_1") (pintype "passive"))
      (node (ref "D11") (pin "1") (pinfunction "K_1") (pintype "passive"))
      (node (ref "Q18") (pin "1") (pinfunction "G_1") (pintype "passive"))
    )
    (net (code "116") (name "Net-(DBD_1-A)") (class "Default")
      (node (ref "DBD_1") (pin "2") (pinfunction "A_2") (pintype "passive"))
      (node (ref "DBD_2") (pin "1") (pinfunction "K_1") (pintype "passive"))
    )
    (net (code "117") (name "Net-(DC5-A)") (class "Default")
      (node (ref "DC5") (pin "2") (pinfunction "A_2") (pintype "passive"))
      (node (ref "RC5A") (pin "1") (pinfunction "1_1") (pintype "passive"))
      (node (ref "U1") (pin "36") (pinfunction "VC5_36") (pintype "passive"))
    )
    (net (code "118") (name "Net-(DC10-A)") (class "Default")
      (node (ref "DC10") (pin "2") (pinfunction "A_2") (pintype "passive"))
      (node (ref "RC10A") (pin "1") (pinfunction "1_1") (pintype "passive"))
      (node (ref "U1") (pin "30") (pinfunction "VC10_30") (pintype "passive"))
    )
    (net (code "119") (name "Net-(DC15-A)") (class "Default")
      (node (ref "CC15") (pin "1") (pinfunction "1_1") (pintype "passive"))
      (node (ref "DC15") (pin "2") (pinfunction "A_2") (pintype "passive"))
      (node (ref "U1") (pin "24") (pinfunction "VC15_24") (pintype "passive"))
    )
    (net (code "120") (name "Net-(DC15-K)") (class "Default")
      (node (ref "DC15") (pin "1") (pinfunction "K_1") (pintype "passive"))
      (node (ref "U1") (pin "20") (pinfunction "BAT_20") (pintype "passive"))
    )
    (net (code "121") (name "Net-(DSHUNT-A)") (class "Default")
      (node (ref "DSHUNT") (pin "2") (pinfunction "A_2") (pintype "passive"))
      (node (ref "QSHUNT") (pin "2") (pinfunction "S_2") (pintype "passive"))
      (node (ref "RSHUNT2") (pin "2") (pinfunction "2_2") (pintype "passive"))
    )
    (net (code "122") (name "Net-(DSHUNT-K)") (class "Default")
      (node (ref "DSHUNT") (pin "1") (pinfunction "K_1") (pintype "passive"))
      (node (ref "RSHUNT2") (pin "1") (pinfunction "1_1") (pintype "passive"))
      (node (ref "RSHUNT3") (pin "2") (pinfunction "2_2") (pintype "passive"))
    )
    (net (code "123") (name "Net-(DS_1-A)") (class "Default")
      (node (ref "DS_1") (pin "2") (pinfunction "A_2") (pintype "passive"))
      (node (ref "DS_2") (pin "1") (pinfunction "K_1") (pintype "passive"))
    )
    (net (code "124") (name "Net-(DS_2-A)") (class "Default")
      (node (ref "DS_2") (pin "2") (pinfunction "A_2") (pintype "passive"))
      (node (ref "DS_3") (pin "1") (pinfunction "K_1") (pintype "passive"))
    )
    (net (code "125") (name "Net-(DS_3-A)") (class "Default")
      (node (ref "DS_3") (pin "2") (pinfunction "A_2") (pintype "passive"))
      (node (ref "DS_4") (pin "1") (pinfunction "K_1") (pintype "passive"))
    )
    (net (code "126") (name "Net-(DS_4-A)") (class "Default")
      (node (ref "DS_4") (pin "2") (pinfunction "A_2") (pintype "passive"))
      (node (ref "DS_5") (pin "1") (pinfunction "K_1") (pintype "passive"))
    )
    (net (code "127") (name "Net-(DS_5-A)") (class "Default")
      (node (ref "DS_5") (pin "2") (pinfunction "A_2") (pintype "passive"))
      (node (ref "DS_6") (pin "1") (pinfunction "K_1") (pintype "passive"))
    )
    (net (code "128") (name "Net-(DS_6-A)") (class "Default")
      (node (ref "DS_6") (pin "2") (pinfunction "A_2") (pintype "passive"))
      (node (ref "RS_0") (pin "2") (pinfunction "2_2") (pintype "passive"))
      (node (ref "RS_1") (pin "2") (pinfunction "2_2") (pintype "passive"))
      (node (ref "RS_2") (pin "2") (pinfunction "2_2") (pintype "passive"))
      (node (ref "RS_3") (pin "2") (pinfunction "2_2") (pintype "passive"))
      (node (ref "RS_4") (pin "2") (pinfunction "2_2") (pintype "passive"))
      (node (ref "RS_5") (pin "2") (pinfunction "2_2") (pintype "passive"))
      (node (ref "RS_6") (pin "2") (pinfunction "2_2") (pintype "passive"))
      (node (ref "RS_7") (pin "2") (pinfunction "2_2") (pintype "passive"))
      (node (ref "RS_8") (pin "2") (pinfunction "2_2") (pintype "passive"))
      (node (ref "RS_9") (pin "2") (pinfunction "2_2") (pintype "passive"))
      (node (ref "R_CMOS") (pin "1") (pinfunction "1_1") (pintype "passive"))
    )
    (net (code "129") (name "Net-(LED_1-K)") (class "Default")
      (node (ref "LED_1") (pin "1") (pinfunction "K_1") (pintype "passive"))
      (node (ref "RLED_1") (pin "1") (pinfunction "1_1") (pintype "passive"))
    )
    (net (code "130") (name "Net-(LED_2-K)") (class "Default")
      (node (ref "LED_2") (pin "1") (pinfunction "K_1") (pintype "passive"))
      (node (ref "RLED_2") (pin "1") (pinfunction "1_1") (pintype "passive"))
    )
    (net (code "131") (name "Net-(LED_3-K)") (class "Default")
      (node (ref "LED_3") (pin "1") (pinfunction "K_1") (pintype "passive"))
      (node (ref "RLED_3") (pin "1") (pinfunction "1_1") (pintype "passive"))
    )
    (net (code "132") (name "Net-(LED_4-K)") (class "Default")
      (node (ref "LED_4") (pin "1") (pinfunction "K_1") (pintype "passive"))
      (node (ref "RLED_4") (pin "1") (pinfunction "1_1") (pintype "passive"))
    )
    (net (code "133") (name "Net-(Q10-S)") (class "Default")
      (node (ref "Q10") (pin "2") (pinfunction "S_2") (pintype "passive"))
      (node (ref "Q11") (pin "3") (pinfunction "D_3") (pintype "passive"))
    )
    (net (code "134") (name "Net-(Q11-S)") (class "Default")
      (node (ref "C10") (pin "1") (pinfunction "1_1") (pintype "passive"))
      (node (ref "Q11") (pin "2") (pinfunction "S_2") (pintype "passive"))
      (node (ref "Q12") (pin "3") (pinfunction "D_3") (pintype "passive"))
      (node (ref "Q13") (pin "3") (pinfunction "D_3") (pintype "passive"))
    )
    (net (code "135") (name "Net-(Q14-G)") (class "Default")
      (node (ref "C10") (pin "2") (pinfunction "2_2") (pintype "passive"))
      (node (ref "Q14") (pin "1") (pinfunction "G_1") (pintype "passive"))
      (node (ref "Q15") (pin "1") (pinfunction "G_1") (pintype "passive"))
      (node (ref "R10") (pin "1") (pinfunction "1_1") (pintype "passive"))
    )
    (net (code "136") (name "Net-(Q15-D)") (class "Default")
      (node (ref "Q15") (pin "3") (pinfunction "D_3") (pintype "passive"))
      (node (ref "R11") (pin "2") (pinfunction "2_2") (pintype "passive"))
    )
    (net (code "137") (name "Net-(Q18-D)") (class "Default")
      (node (ref "Q18") (pin "3") (pinfunction "D_3") (pintype "passive"))
      (node (ref "Q19") (pin "1") (pinfunction "G_1") (pintype "passive"))
      (node (ref "R18") (pin "2") (pinfunction "2_2") (pintype "passive"))
    )
    (net (code "138") (name "Net-(Q19-D)") (class "Default")
      (node (ref "Q19") (pin "3") (pinfunction "D_3") (pintype "passive"))
      (node (ref "R18") (pin "1") (pinfunction "1_1") (pintype "passive"))
      (node (ref "RS_20") (pin "1") (pinfunction "1_1") (pintype "passive"))
      (node (ref "RS_21") (pin "1") (pinfunction "1_1") (pintype "passive"))
      (node (ref "RS_22") (pin "1") (pinfunction "1_1") (pintype "passive"))
      (node (ref "RS_23") (pin "1") (pinfunction "1_1") (pintype "passive"))
      (node (ref "RS_24") (pin "1") (pinfunction "1_1") (pintype "passive"))
      (node (ref "RS_25") (pin "1") (pinfunction "1_1") (pintype "passive"))
      (node (ref "RS_26") (pin "1") (pinfunction "1_1") (pintype "passive"))
      (node (ref "RS_27") (pin "1") (pinfunction "1_1") (pintype "passive"))
      (node (ref "RS_28") (pin "1") (pinfunction "1_1") (pintype "passive"))
      (node (ref "RS_29") (pin "1") (pinfunction "1_1") (pintype "passive"))
    )
    (net (code "139") (name "Net-(QBEN-D)") (class "Default")
      (node (ref "QBEN") (pin "3") (pinfunction "D_3") (pintype "passive"))
      (node (ref "RBEN") (pin "1") (pinfunction "1_1") (pintype "passive"))
    )
    (net (code "140") (name "Net-(QSHUNT-G)") (class "Default")
      (node (ref "QSHUNT") (pin "1") (pinfunction "G_1") (pintype "passive"))
      (node (ref "RSHUNT") (pin "2") (pinfunction "2_2") (pintype "passive"))
    )
    (net (code "141") (name "Net-(Q_3V3-G)") (class "Default")
      (node (ref "3V3R1") (pin "2") (pinfunction "2_2") (pintype "passive"))
      (node (ref "3V3R2") (pin "1") (pinfunction "1_1") (pintype "passive"))
      (node (ref "Q_3V3") (pin "1") (pinfunction "G_1") (pintype "passive"))
    )
    (net (code "142") (name "Net-(RBUS_1-Pad1)") (class "Default")
      (node (ref "RBUS_1") (pin "1") (pinfunction "1_1") (pintype "passive"))
      (node (ref "RBUS_2") (pin "2") (pinfunction "2_2") (pintype "passive"))
    )
    (net (code "143") (name "Net-(RS_0-Pad1)") (class "Default")
      (node (ref "RS_0") (pin "1") (pinfunction "1_1") (pintype "passive"))
      (node (ref "RS_10") (pin "2") (pinfunction "2_2") (pintype "passive"))
    )
    (net (code "144") (name "Net-(RS_1-Pad1)") (class "Default")
      (node (ref "RS_1") (pin "1") (pinfunction "1_1") (pintype "passive"))
      (node (ref "RS_11") (pin "2") (pinfunction "2_2") (pintype "passive"))
    )
    (net (code "145") (name "Net-(RS_10-Pad1)") (class "Default")
      (node (ref "RS_10") (pin "1") (pinfunction "1_1") (pintype "passive"))
      (node (ref "RS_20") (pin "2") (pinfunction "2_2") (pintype "passive"))
    )
    (net (code "146") (name "Net-(RS_11-Pad1)") (class "Default")
      (node (ref "RS_11") (pin "1") (pinfunction "1_1") (pintype "passive"))
      (node (ref "RS_21") (pin "2") (pinfunction "2_2") (pintype "passive"))
    )
    (net (code "147") (name "Net-(RS_12-Pad1)") (class "Default")
      (node (ref "RS_12") (pin "1") (pinfunction "1_1") (pintype "passive"))
      (node (ref "RS_22") (pin "2") (pinfunction "2_2") (pintype "passive"))
    )
    (net (code "148") (name "Net-(RS_12-Pad2)") (class "Default")
      (node (ref "RS_12") (pin "2") (pinfunction "2_2") (pintype "passive"))
      (node (ref "RS_2") (pin "1") (pinfunction "1_1") (pintype "passive"))
    )
    (net (code "149") (name "Net-(RS_13-Pad1)") (class "Default")
      (node (ref "RS_13") (pin "1") (pinfunction "1_1") (pintype "passive"))
      (node (ref "RS_23") (pin "2") (pinfunction "2_2") (pintype "passive"))
    )
    (net (code "150") (name "Net-(RS_13-Pad2)") (class "Default")
      (node (ref "RS_13") (pin "2") (pinfunction "2_2") (pintype "passive"))
      (node (ref "RS_3") (pin "1") (pinfunction "1_1") (pintype "passive"))
    )
    (net (code "151") (name "Net-(RS_14-Pad1)") (class "Default")
      (node (ref "RS_14") (pin "1") (pinfunction "1_1") (pintype "passive"))
      (node (ref "RS_24") (pin "2") (pinfunction "2_2") (pintype "passive"))
    )
    (net (code "152") (name "Net-(RS_14-Pad2)") (class "Default")
      (node (ref "RS_14") (pin "2") (pinfunction "2_2") (pintype "passive"))
      (node (ref "RS_4") (pin "1") (pinfunction "1_1") (pintype "passive"))
    )
    (net (code "153") (name "Net-(RS_15-Pad1)") (class "Default")
      (node (ref "RS_15") (pin "1") (pinfunction "1_1") (pintype "passive"))
      (node (ref "RS_25") (pin "2") (pinfunction "2_2") (pintype "passive"))
    )
    (net (code "154") (name "Net-(RS_15-Pad2)") (class "Default")
      (node (ref "RS_15") (pin "2") (pinfunction "2_2") (pintype "passive"))
      (node (ref "RS_5") (pin "1") (pinfunction "1_1") (pintype "passive"))
    )
    (net (code "155") (name "Net-(RS_16-Pad1)") (class "Default")
      (node (ref "RS_16") (pin "1") (pinfunction "1_1") (pintype "passive"))
      (node (ref "RS_26") (pin "2") (pinfunction "2_2") (pintype "passive"))
    )
    (net (code "156") (name "Net-(RS_16-Pad2)") (class "Default")
      (node (ref "RS_16") (pin "2") (pinfunction "2_2") (pintype "passive"))
      (node (ref "RS_6") (pin "1") (pinfunction "1_1") (pintype "passive"))
    )
    (net (code "157") (name "Net-(RS_17-Pad1)") (class "Default")
      (node (ref "RS_17") (pin "1") (pinfunction "1_1") (pintype "passive"))
      (node (ref "RS_27") (pin "2") (pinfunction "2_2") (pintype "passive"))
    )
    (net (code "158") (name "Net-(RS_17-Pad2)") (class "Default")
      (node (ref "RS_17") (pin "2") (pinfunction "2_2") (pintype "passive"))
      (node (ref "RS_7") (pin "1") (pinfunction "1_1") (pintype "passive"))
    )
    (net (code "159") (name "Net-(RS_18-Pad1)") (class "Default")
      (node (ref "RS_18") (pin "1") (pinfunction "1_1") (pintype "passive"))
      (node (ref "RS_28") (pin "2") (pinfunction "2_2") (pintype "passive"))
    )
    (net (code "160") (name "Net-(RS_18-Pad2)") (class "Default")
      (node (ref "RS_18") (pin "2") (pinfunction "2_2") (pintype "passive"))
      (node (ref "RS_8") (pin "1") (pinfunction "1_1") (pintype "passive"))
    )
    (net (code "161") (name "Net-(RS_19-Pad1)") (class "Default")
      (node (ref "RS_19") (pin "1") (pinfunction "1_1") (pintype "passive"))
      (node (ref "RS_29") (pin "2") (pinfunction "2_2") (pintype "passive"))
    )
    (net (code "162") (name "Net-(RS_19-Pad2)") (class "Default")
      (node (ref "RS_19") (pin "2") (pinfunction "2_2") (pintype "passive"))
      (node (ref "RS_9") (pin "1") (pinfunction "1_1") (pintype "passive"))
    )
    (net (code "163") (name "Net-(U1-CAP1)") (class "Default")
      (node (ref "CAP1") (pin "1") (pinfunction "1_1") (pintype "passive"))
      (node (ref "U1") (pin "7") (pinfunction "CAP1_7") (pintype "passive"))
    )
    (net (code "164") (name "Net-(U1-CAP2)") (class "Default")
      (node (ref "CAP2") (pin "1") (pinfunction "1_1") (pintype "passive"))
      (node (ref "U1") (pin "11") (pinfunction "NC_11") (pintype "passive"))
      (node (ref "U1") (pin "12") (pinfunction "NC_12") (pintype "passive"))
      (node (ref "U1") (pin "14") (pinfunction "CAP2_14") (pintype "passive"))
    )
    (net (code "165") (name "Net-(U1-CAP3)") (class "Default")
      (node (ref "CAP3") (pin "1") (pinfunction "1_1") (pintype "passive"))
      (node (ref "U1") (pin "16") (pinfunction "NC_16") (pintype "passive"))
      (node (ref "U1") (pin "17") (pinfunction "NC_17") (pintype "passive"))
      (node (ref "U1") (pin "19") (pinfunction "CAP3_19") (pintype "passive"))
    )
    (net (code "166") (name "Net-(U1-VC0)") (class "Default")
      (node (ref "RC0") (pin "1") (pinfunction "1_1") (pintype "passive"))
      (node (ref "U1") (pin "41") (pinfunction "VC0_41") (pintype "passive"))
    )
    (net (code "167") (name "Net-(U1-VC1)") (class "Default")
      (node (ref "RC1") (pin "1") (pinfunction "1_1") (pintype "passive"))
      (node (ref "U1") (pin "40") (pinfunction "VC1_40") (pintype "passive"))
    )
    (net (code "168") (name "Net-(U1-VC2)") (class "Default")
      (node (ref "RC2") (pin "1") (pinfunction "1_1") (pintype "passive"))
      (node (ref "U1") (pin "39") (pinfunction "VC2_39") (pintype "passive"))
    )
    (net (code "169") (name "Net-(U1-VC3)") (class "Default")
      (node (ref "RC3") (pin "1") (pinfunction "1_1") (pintype "passive"))
      (node (ref "U1") (pin "38") (pinfunction "VC3_38") (pintype "passive"))
    )
    (net (code "170") (name "Net-(U1-VC4)") (class "Default")
      (node (ref "RC4") (pin "1") (pinfunction "1_1") (pintype "passive"))
      (node (ref "U1") (pin "37") (pinfunction "VC4_37") (pintype "passive"))
    )
    (net (code "171") (name "Net-(U1-VC5B)") (class "Default")
      (node (ref "RC5B") (pin "1") (pinfunction "1_1") (pintype "passive"))
      (node (ref "U1") (pin "35") (pinfunction "VC5B_35") (pintype "passive"))
    )
    (net (code "172") (name "Net-(U1-VC6)") (class "Default")
      (node (ref "RC6") (pin "1") (pinfunction "1_1") (pintype "passive"))
      (node (ref "U1") (pin "34") (pinfunction "VC6_34") (pintype "passive"))
    )
    (net (code "173") (name "Net-(U1-VC7)") (class "Default")
      (node (ref "RC7") (pin "1") (pinfunction "1_1") (pintype "passive"))
      (node (ref "U1") (pin "33") (pinfunction "VC7_33") (pintype "passive"))
    )
    (net (code "174") (name "Net-(U1-VC8)") (class "Default")
      (node (ref "RC8") (pin "1") (pinfunction "1_1") (pintype "passive"))
      (node (ref "U1") (pin "32") (pinfunction "VC8_32") (pintype "passive"))
    )
    (net (code "175") (name "Net-(U1-VC9)") (class "Default")
      (node (ref "RC9") (pin "1") (pinfunction "1_1") (pintype "passive"))
      (node (ref "U1") (pin "31") (pinfunction "VC9_31") (pintype "passive"))
    )
    (net (code "176") (name "Net-(U1-VC10B)") (class "Default")
      (node (ref "RC10B") (pin "1") (pinfunction "1_1") (pintype "passive"))
      (node (ref "U1") (pin "29") (pinfunction "VC10B_29") (pintype "passive"))
    )
    (net (code "177") (name "Net-(U1-VC11)") (class "Default")
      (node (ref "RC11") (pin "1") (pinfunction "1_1") (pintype "passive"))
      (node (ref "U1") (pin "28") (pinfunction "VC11_28") (pintype "passive"))
    )
    (net (code "178") (name "Net-(U1-VC12)") (class "Default")
      (node (ref "RC12") (pin "1") (pinfunction "1_1") (pintype "passive"))
      (node (ref "U1") (pin "27") (pinfunction "VC12_27") (pintype "passive"))
    )
    (net (code "179") (name "Net-(U1-VC13)") (class "Default")
      (node (ref "RC13") (pin "1") (pinfunction "1_1") (pintype "passive"))
      (node (ref "U1") (pin "26") (pinfunction "VC13_26") (pintype "passive"))
    )
    (net (code "180") (name "Net-(U1-VC14)") (class "Default")
      (node (ref "RC14") (pin "1") (pinfunction "1_1") (pintype "passive"))
      (node (ref "U1") (pin "25") (pinfunction "VC14_25") (pintype "passive"))
    )
    (net (code "181") (name "Net-(U100-PD0-OSC_IN)") (class "Default")
      (node (ref "C100") (pin "2") (pinfunction "2_2") (pintype "passive"))
      (node (ref "U100") (pin "5") (pinfunction "PD0-OSC_IN_5") (pintype "bidirectional"))
      (node (ref "Y100") (pin "1") (pintype "passive"))
    )
    (net (code "182") (name "Net-(U100-PD1-OSC_OUT)") (class "Default")
      (node (ref "C101") (pin "2") (pinfunction "2_2") (pintype "passive"))
      (node (ref "U100") (pin "6") (pinfunction "PD1-OSC_OUT_6") (pintype "bidirectional"))
      (node (ref "Y100") (pin "2") (pintype "passive"))
    )
    (net (code "183") (name "unconnected-(J100-SBU1-PadA8)") (class "Default")
      (node (ref "J100") (pin "A8") (pinfunction "SBU1_A8") (pintype "passive"))
    )
    (net (code "184") (name "unconnected-(J100-SBU2-PadB8)") (class "Default")
      (node (ref "J100") (pin "B8") (pinfunction "SBU2_B8") (pintype "passive"))
    )
    (net (code "185") (name "unconnected-(U1-CHG-Pad2)") (class "Default")
      (node (ref "U1") (pin "2") (pinfunction "CHG_2") (pintype "passive"))
    )
    (net (code "186") (name "unconnected-(U1-DSG-Pad1)") (class "Default")
      (node (ref "U1") (pin "1") (pinfunction "DSG_1") (pintype "passive"))
    )
    (net (code "187") (name "unconnected-(U1-NC-Pad21)") (class "Default")
      (node (ref "U1") (pin "21") (pinfunction "NC_21") (pintype "passive"))
    )
    (net (code "188") (name "unconnected-(U1-NC-Pad22)") (class "Default")
      (node (ref "U1") (pin "22") (pinfunction "NC_22") (pintype "passive"))
    )
    (net (code "189") (name "unconnected-(U1-NC-Pad23)") (class "Default")
      (node (ref "U1") (pin "23") (pinfunction "NC_23") (pintype "passive"))
    )
  )
)
